# design.net
KiCad netlist of a schematic drawn in Altium Designer
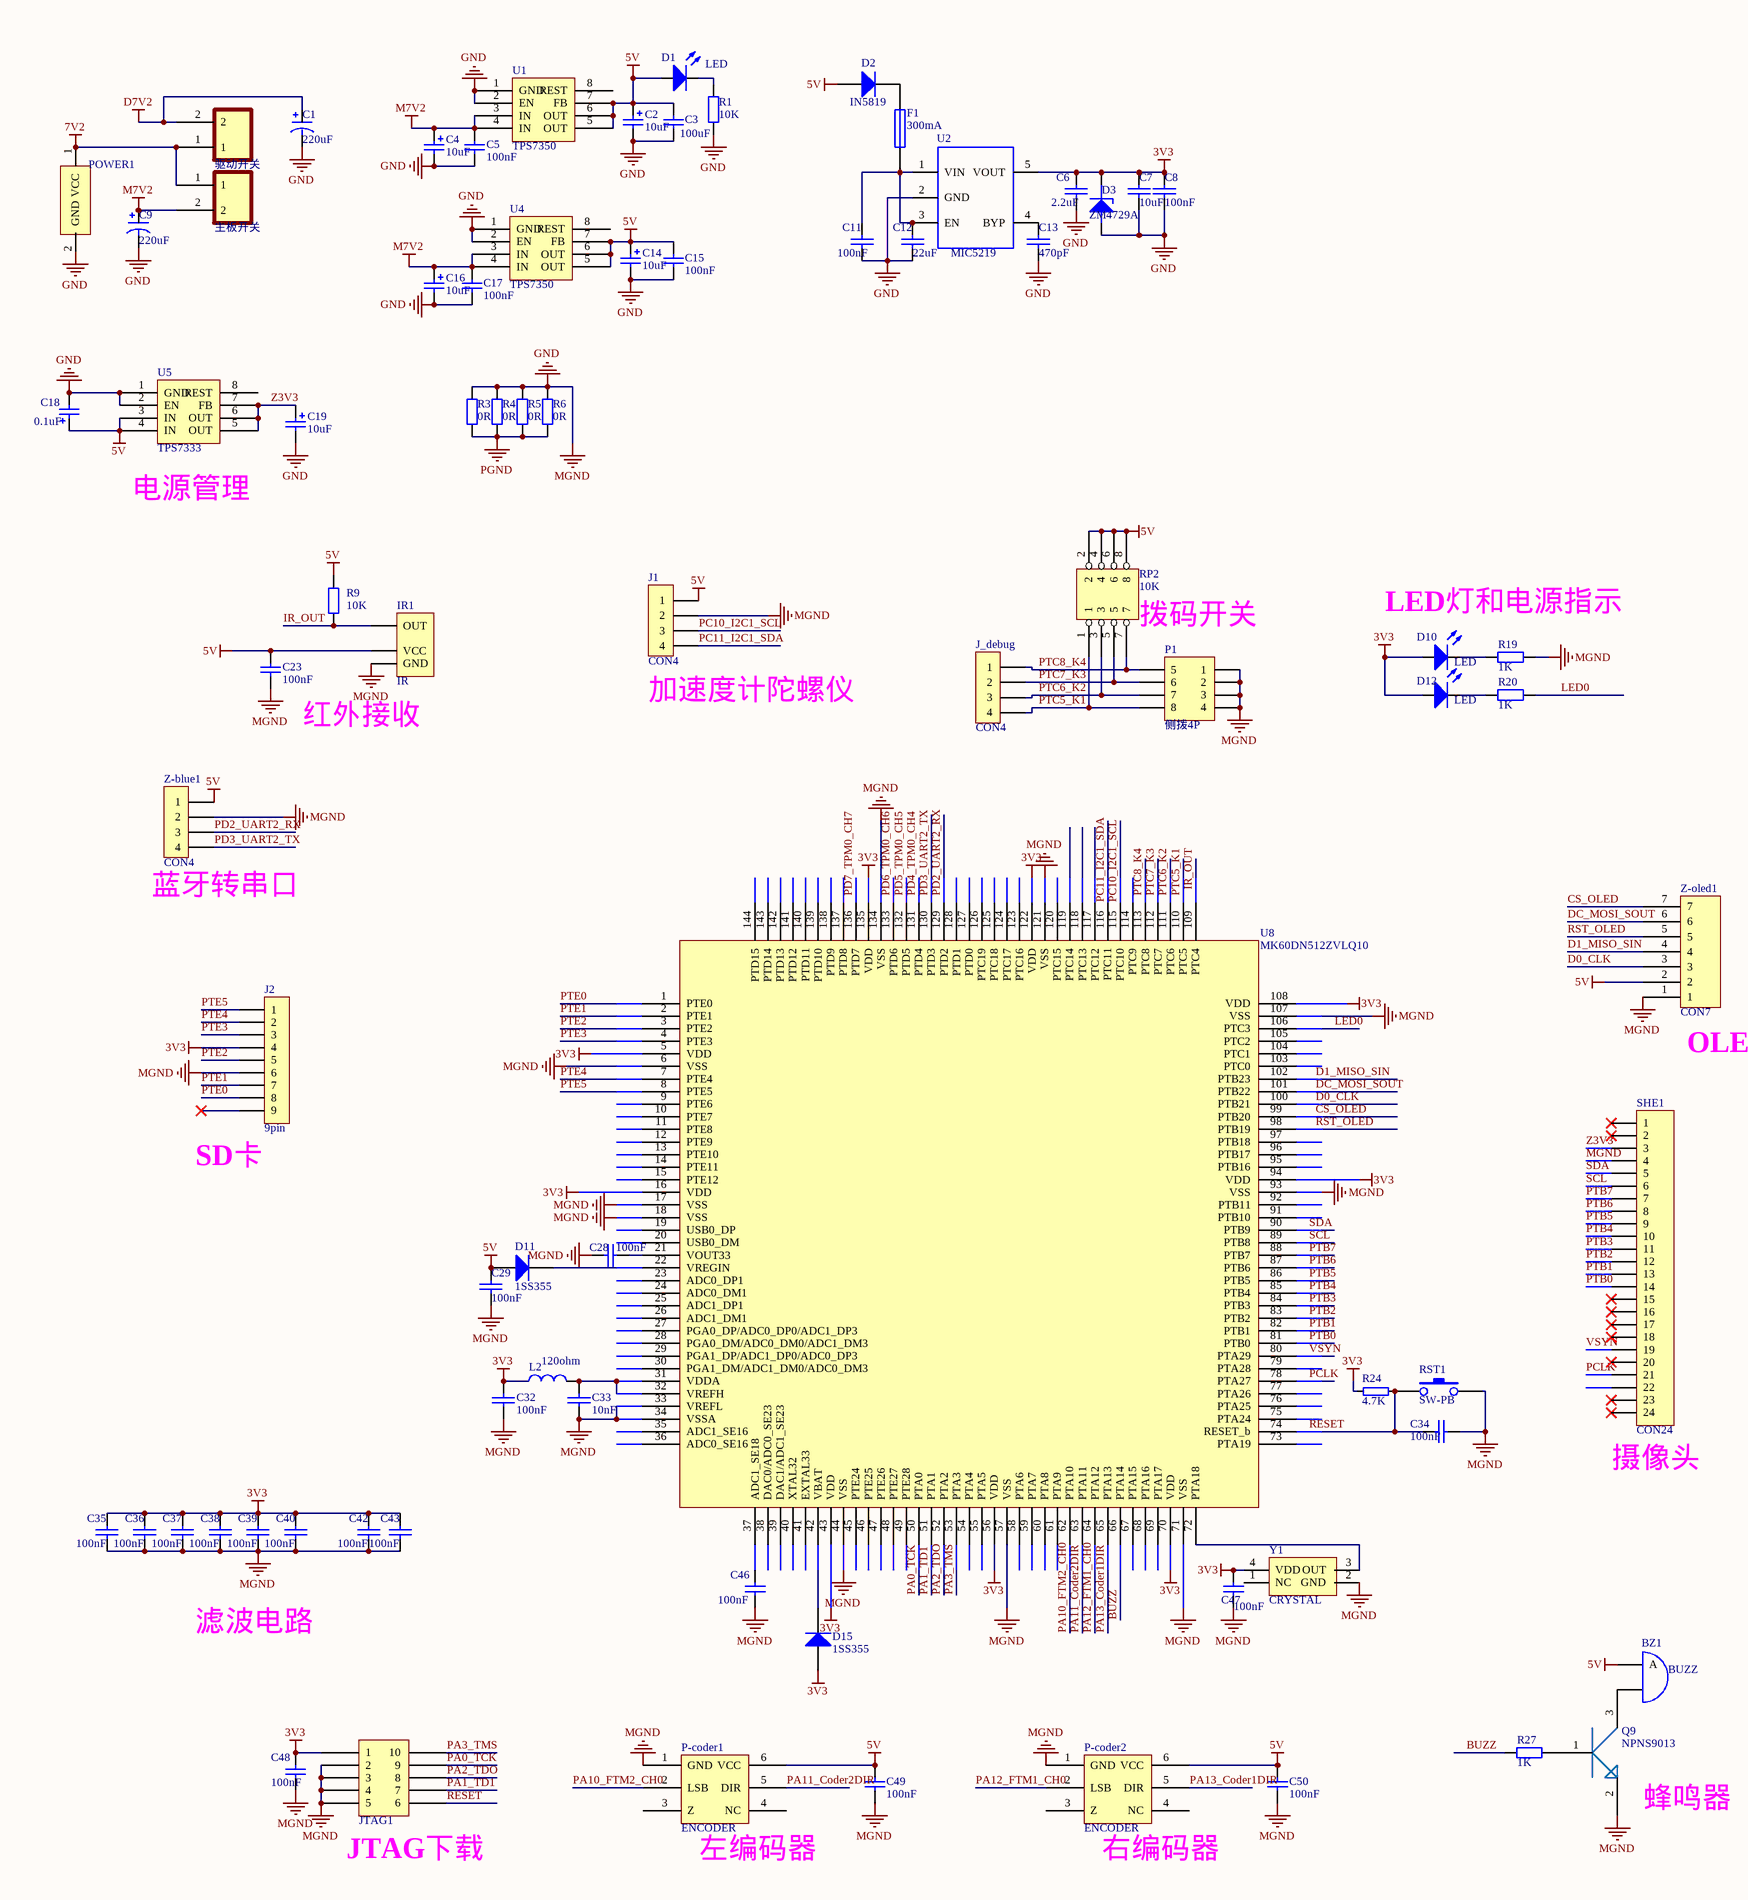
[diagram p0: 第十二届直立摄像头.SchDoc, left]
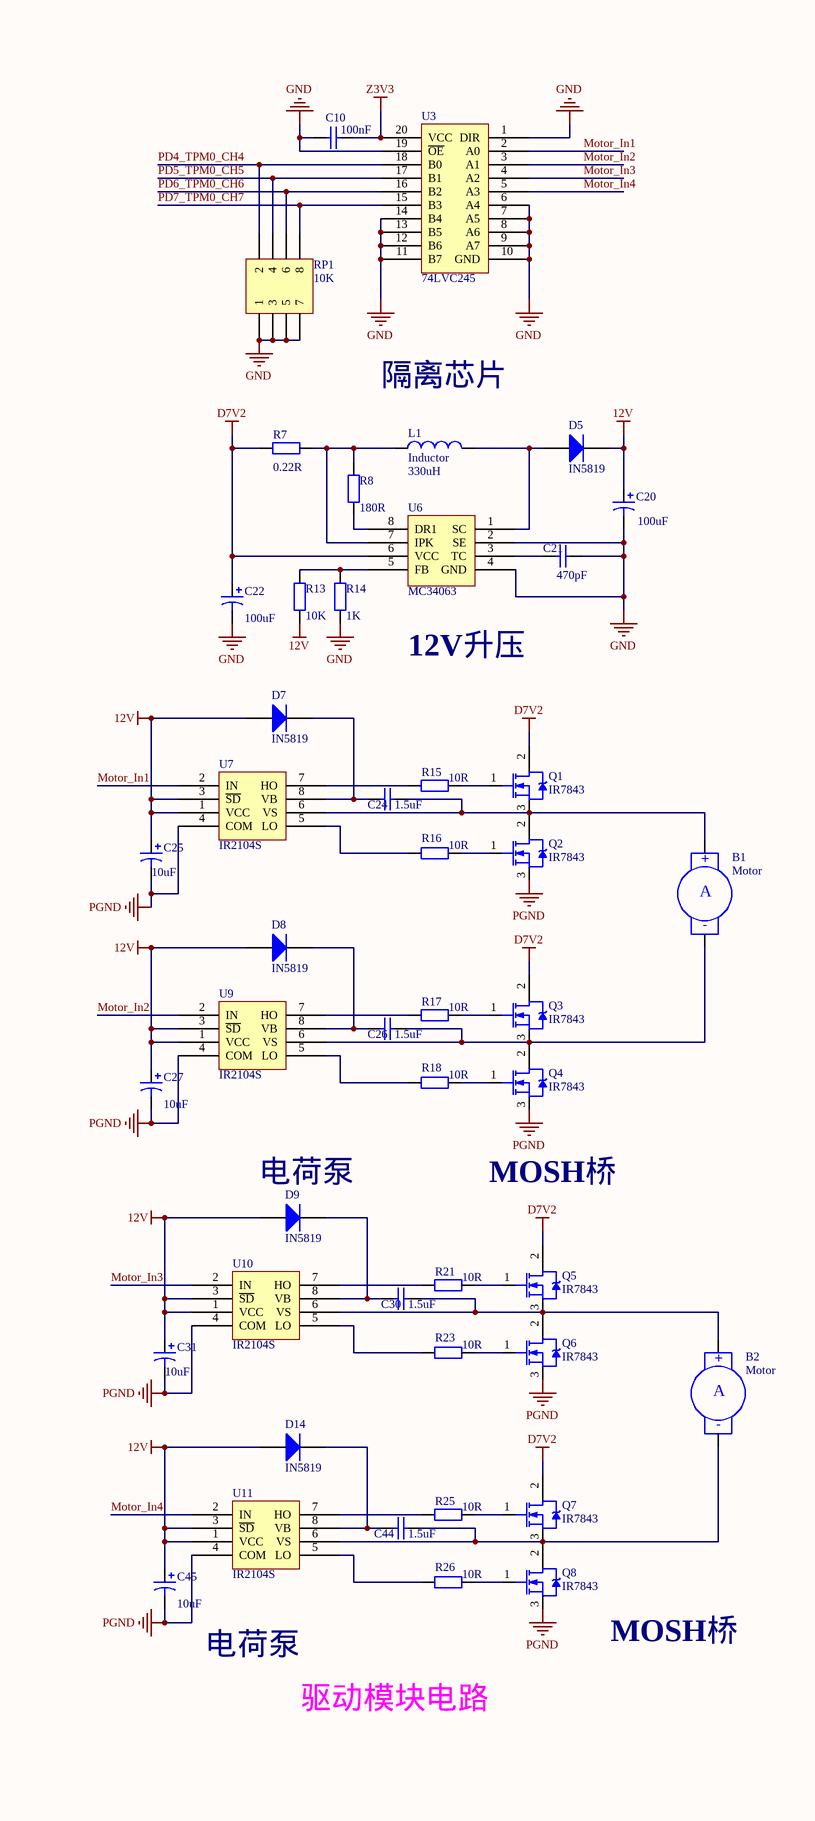
[diagram p1: 第十二届直立摄像头.SchDoc, right]

(export (version "E")
  (design (tool "Eeschema 10.0.6"))
  (components
    (comp (ref "B1")
      (value "Motor")
      (footprint "KF301-2P")
      (description "Servo Motor")
      (libsource (lib "MOS motor driving module ") (part "Motor Servo"))
    )
    (comp (ref "B2")
      (value "Motor")
      (footprint "KF301-2P")
      (description "Servo Motor")
      (libsource (lib "MOS motor driving module ") (part "Motor Servo"))
    )
    (comp (ref "BZ1") (value "BUZZ") (footprint "BUZZ") (libsource (lib "原理图库") (part "BUZZ")))
    (comp (ref "C1")
      (value "CAP2")
      (footprint "铝电解电容10*10.2")
      (description "电容带极性")
      (fields (field (name "ALTIUM_UNNAMED_1") "220uF"))
      (libsource (lib "原理图库") (part "CAP2"))
    )
    (comp (ref "C2") (value "10uF") (footprint "3216") (libsource (lib "飞思卡尔") (part "电容")))
    (comp (ref "C3")
      (value "100uF")
      (footprint "0603(1608)")
      (description "Capacitor")
      (libsource (lib "最小系统板K60P144-V4.0") (part "Cap"))
    )
    (comp (ref "C4") (value "10uF") (footprint "3216") (libsource (lib "飞思卡尔") (part "电容")))
    (comp (ref "C5")
      (value "100nF")
      (footprint "0603(1608)")
      (description "Capacitor")
      (libsource (lib "最小系统板K60P144-V4.0") (part "Cap"))
    )
    (comp (ref "C6")
      (value "2.2uF")
      (footprint "0603(1608)")
      (description "Capacitor")
      (libsource (lib "K60芯片") (part "普通电容"))
    )
    (comp (ref "C7")
      (value "10uF")
      (footprint "0603(1608)")
      (description "Capacitor")
      (libsource (lib "K60芯片") (part "普通电容"))
    )
    (comp (ref "C8")
      (value "100nF")
      (footprint "0603(1608)")
      (description "Capacitor")
      (libsource (lib "K60芯片") (part "普通电容"))
    )
    (comp (ref "C9")
      (value "CAP2")
      (footprint "铝电解电容10*10.2")
      (description "电容带极性")
      (fields (field (name "ALTIUM_UNNAMED_1") "220uF"))
      (libsource (lib "原理图库") (part "CAP2"))
    )
    (comp (ref "C10")
      (value "100nF")
      (footprint "0603(1608)")
      (description "Capacitor")
      (fields (field (name "Comment") "Cap") (field (name "PUBLISHER") "Altium Limited"))
      (libsource (lib "Miscellaneous Devices") (part "Cap"))
    )
    (comp (ref "C11")
      (value "100nF")
      (footprint "0603(1608)")
      (description "Capacitor")
      (libsource (lib "K60芯片") (part "普通电容"))
    )
    (comp (ref "C12")
      (value "22uF")
      (footprint "0603(1608)")
      (description "Capacitor")
      (libsource (lib "K60芯片") (part "普通电容"))
    )
    (comp (ref "C13")
      (value "470pF")
      (footprint "0603(1608)")
      (description "Capacitor")
      (libsource (lib "K60芯片") (part "普通电容"))
    )
    (comp (ref "C14") (value "10uF") (footprint "3216") (libsource (lib "飞思卡尔") (part "电容")))
    (comp (ref "C15")
      (value "100nF")
      (footprint "0603(1608)")
      (description "Capacitor")
      (libsource (lib "最小系统板K60P144-V4.0") (part "Cap"))
    )
    (comp (ref "C16") (value "10uF") (footprint "3216") (libsource (lib "飞思卡尔") (part "电容")))
    (comp (ref "C17")
      (value "100nF")
      (footprint "0603(1608)")
      (description "Capacitor")
      (libsource (lib "最小系统板K60P144-V4.0") (part "Cap"))
    )
    (comp (ref "C18") (value "0.1uF") (footprint "3216") (libsource (lib "飞思卡尔") (part "电容")))
    (comp (ref "C19") (value "10uF") (footprint "3216") (libsource (lib "飞思卡尔") (part "电容")))
    (comp (ref "C20")
      (value "100uF")
      (footprint "TAN-D7343")
      (description "Polarized Capacitor (Radial)")
      (fields (field (name "Comment") "Cap Pol1") (field (name "PUBLISHER") "Altium Limited"))
      (libsource (lib "Miscellaneous Devices") (part "Cap Pol1"))
    )
    (comp (ref "C21")
      (value "470pF")
      (footprint "0603(1608)")
      (description "Capacitor")
      (fields (field (name "Comment") "Cap") (field (name "PUBLISHER") "Altium Limited"))
      (libsource (lib "Miscellaneous Devices") (part "Cap"))
    )
    (comp (ref "C22")
      (value "100uF")
      (footprint "TAN-D7343")
      (description "Polarized Capacitor (Radial)")
      (fields (field (name "Comment") "Cap Pol1") (field (name "PUBLISHER") "Altium Limited"))
      (libsource (lib "Miscellaneous Devices") (part "Cap Pol1"))
    )
    (comp (ref "C23")
      (value "100nF")
      (footprint "0603(1608)")
      (description "Capacitor")
      (fields (field (name "PUBLISHER") "Altium Limited"))
      (libsource (lib "国特原理图库") (part "Cap_1"))
    )
    (comp (ref "C24")
      (value "1.5uF")
      (footprint "0603(1608)")
      (description "Capacitor")
      (fields (field (name "Comment") "Cap") (field (name "PUBLISHER") "Altium Limited"))
      (libsource (lib "Miscellaneous Devices") (part "Cap"))
    )
    (comp (ref "C25")
      (value "10uF")
      (footprint "Tan-A3216")
      (description "Polarized Capacitor (Radial)")
      (fields (field (name "Comment") "Cap Pol1") (field (name "PUBLISHER") "Altium Limited"))
      (libsource (lib "Miscellaneous Devices") (part "Cap Pol1"))
    )
    (comp (ref "C26")
      (value "1.5uF")
      (footprint "0603(1608)")
      (description "Capacitor")
      (fields (field (name "Comment") "Cap") (field (name "PUBLISHER") "Altium Limited"))
      (libsource (lib "Miscellaneous Devices") (part "Cap"))
    )
    (comp (ref "C27")
      (value "10uF")
      (footprint "Tan-A3216")
      (description "Polarized Capacitor (Radial)")
      (fields (field (name "Comment") "Cap Pol1") (field (name "PUBLISHER") "Altium Limited"))
      (libsource (lib "Miscellaneous Devices") (part "Cap Pol1"))
    )
    (comp (ref "C28")
      (value "100nF")
      (footprint "0603(1608)")
      (description "Capacitor")
      (libsource (lib "K60芯片") (part "普通电容"))
    )
    (comp (ref "C29")
      (value "100nF")
      (footprint "0603(1608)")
      (description "Capacitor")
      (libsource (lib "K60芯片") (part "普通电容"))
    )
    (comp (ref "C30")
      (value "1.5uF")
      (footprint "0603(1608)")
      (description "Capacitor")
      (fields (field (name "Comment") "Cap") (field (name "PUBLISHER") "Altium Limited"))
      (libsource (lib "Miscellaneous Devices") (part "Cap"))
    )
    (comp (ref "C31")
      (value "10uF")
      (footprint "Tan-A3216")
      (description "Polarized Capacitor (Radial)")
      (fields (field (name "Comment") "Cap Pol1") (field (name "PUBLISHER") "Altium Limited"))
      (libsource (lib "Miscellaneous Devices") (part "Cap Pol1"))
    )
    (comp (ref "C32")
      (value "100nF")
      (footprint "0603(1608)")
      (description "Capacitor")
      (libsource (lib "K60芯片") (part "普通电容"))
    )
    (comp (ref "C33")
      (value "10nF")
      (footprint "0603(1608)")
      (description "Capacitor")
      (libsource (lib "K60芯片") (part "普通电容"))
    )
    (comp (ref "C34")
      (value "100nF")
      (footprint "0603(1608)")
      (description "Capacitor")
      (libsource (lib "K60芯片") (part "普通电容"))
    )
    (comp (ref "C35")
      (value "100nF")
      (footprint "0603(1608)")
      (description "Capacitor")
      (libsource (lib "K60芯片") (part "普通电容"))
    )
    (comp (ref "C36")
      (value "100nF")
      (footprint "0603(1608)")
      (description "Capacitor")
      (libsource (lib "K60芯片") (part "普通电容"))
    )
    (comp (ref "C37")
      (value "100nF")
      (footprint "0603(1608)")
      (description "Capacitor")
      (libsource (lib "K60芯片") (part "普通电容"))
    )
    (comp (ref "C38")
      (value "100nF")
      (footprint "0603(1608)")
      (description "Capacitor")
      (libsource (lib "K60芯片") (part "普通电容"))
    )
    (comp (ref "C39")
      (value "100nF")
      (footprint "0603(1608)")
      (description "Capacitor")
      (libsource (lib "K60芯片") (part "普通电容"))
    )
    (comp (ref "C40")
      (value "100nF")
      (footprint "0603(1608)")
      (description "Capacitor")
      (libsource (lib "K60芯片") (part "普通电容"))
    )
    (comp (ref "C42")
      (value "100nF")
      (footprint "0603(1608)")
      (description "Capacitor")
      (libsource (lib "K60芯片") (part "普通电容"))
    )
    (comp (ref "C43")
      (value "100nF")
      (footprint "0603(1608)")
      (description "Capacitor")
      (libsource (lib "K60芯片") (part "普通电容"))
    )
    (comp (ref "C44")
      (value "1.5uF")
      (footprint "0603(1608)")
      (description "Capacitor")
      (fields (field (name "Comment") "Cap") (field (name "PUBLISHER") "Altium Limited"))
      (libsource (lib "Miscellaneous Devices") (part "Cap"))
    )
    (comp (ref "C45")
      (value "10uF")
      (footprint "Tan-A3216")
      (description "Polarized Capacitor (Radial)")
      (fields (field (name "Comment") "Cap Pol1") (field (name "PUBLISHER") "Altium Limited"))
      (libsource (lib "Miscellaneous Devices") (part "Cap Pol1"))
    )
    (comp (ref "C46")
      (value "100nF")
      (footprint "0603(1608)")
      (description "Capacitor")
      (fields (field (name "PUBLISHER") "Altium Limited"))
      (libsource (lib "国特原理图库") (part "Cap_1"))
    )
    (comp (ref "C47")
      (value "100nF")
      (footprint "0603(1608)")
      (description "Capacitor")
      (fields (field (name "PUBLISHER") "Altium Limited"))
      (libsource (lib "国特原理图库") (part "Cap_1"))
    )
    (comp (ref "C48")
      (value "100nF")
      (footprint "0603(1608)")
      (description "Capacitor")
      (libsource (lib "最小系统板K60P144-V4.0") (part "Cap"))
    )
    (comp (ref "C49")
      (value "100nF")
      (footprint "0603(1608)")
      (description "Capacitor")
      (libsource (lib "最小系统板K60P144-V4.0") (part "Cap"))
    )
    (comp (ref "C50")
      (value "100nF")
      (footprint "0603(1608)")
      (description "Capacitor")
      (libsource (lib "最小系统板K60P144-V4.0") (part "Cap"))
    )
    (comp (ref "D1")
      (value "LED")
      (footprint "0603LED")
      (description "Typical INFRARED GaAs LED")
      (libsource (lib "国特原理图库") (part "LED"))
    )
    (comp (ref "D2")
      (value "IN5819")
      (footprint "SS14")
      (description "Default Diode")
      (fields (field (name "PUBLISHER") "Altium Limited"))
      (libsource (lib "Miscellaneous Devices") (part "Diode"))
    )
    (comp (ref "D3")
      (value "ZM4729A")
      (footprint "LL-41")
      (description "Zener Diode")
      (libsource (lib "K60最小系统") (part "稳压二极管"))
    )
    (comp (ref "D5")
      (value "IN5819")
      (footprint "SS14")
      (description "Default Diode")
      (fields (field (name "PUBLISHER") "Altium Limited"))
      (libsource (lib "Miscellaneous Devices") (part "Diode"))
    )
    (comp (ref "D7")
      (value "IN5819")
      (footprint "SS14")
      (description "Default Diode")
      (fields (field (name "PUBLISHER") "Altium Limited"))
      (libsource (lib "Miscellaneous Devices") (part "Diode"))
    )
    (comp (ref "D8")
      (value "IN5819")
      (footprint "SS14")
      (description "Default Diode")
      (fields (field (name "PUBLISHER") "Altium Limited"))
      (libsource (lib "Miscellaneous Devices") (part "Diode"))
    )
    (comp (ref "D9")
      (value "IN5819")
      (footprint "SS14")
      (description "Default Diode")
      (fields (field (name "PUBLISHER") "Altium Limited"))
      (libsource (lib "Miscellaneous Devices") (part "Diode"))
    )
    (comp (ref "D10")
      (value "LED")
      (footprint "0603LED")
      (description "Typical INFRARED GaAs LED")
      (libsource (lib "国特原理图库") (part "LED"))
    )
    (comp (ref "D11")
      (value "1SS355")
      (footprint "0805(有极性)")
      (description "High Conductance Fast Diode")
      (fields (field (name "PUBLISHER") "Altium Limited"))
      (libsource (lib "最小系统板K60P144-V4.0") (part "Diode 1N4148"))
    )
    (comp (ref "D12")
      (value "LED")
      (footprint "0603LED")
      (description "Typical INFRARED GaAs LED")
      (libsource (lib "国特原理图库") (part "LED"))
    )
    (comp (ref "D14")
      (value "IN5819")
      (footprint "SS14")
      (description "Default Diode")
      (fields (field (name "PUBLISHER") "Altium Limited"))
      (libsource (lib "Miscellaneous Devices") (part "Diode"))
    )
    (comp (ref "D15")
      (value "1SS355")
      (footprint "0805(有极性)")
      (description "High Conductance Fast Diode")
      (fields (field (name "PUBLISHER") "Altium Limited"))
      (libsource (lib "最小系统板K60P144-V4.0") (part "Diode 1N4148"))
    )
    (comp (ref "F1")
      (value "300mA")
      (footprint "保险丝")
      (description "Fuse")
      (fields (field (name "PUBLISHER") "Altium Limited"))
      (libsource (lib "最小系统板K60P144-V4.0") (part "Fuse 1"))
    )
    (comp (ref "IR1") (value "IR") (footprint "IR2") (libsource (lib "原理图库") (part "IR_2")))
    (comp (ref "J1") (value "CON4") (footprint "CON4-1") (libsource (lib "原理图库") (part "CON4")))
    (comp (ref "J2") (value "9pin") (footprint "SD") (libsource (lib "zrobot_sch_lib") (part "9pin")))
    (comp (ref "JTAG1") (value "JTAG") (footprint "IDC5X2") (libsource (lib "国特原理图库") (part "JTAG")))
    (comp (ref "J_debug") (value "CON4") (footprint "CON4-1") (libsource (lib "原理图库") (part "CON4")))
    (comp (ref "L1")
      (value "Inductor")
      (footprint "贴片电感7*7*4")
      (fields (field (name "ALTIUM_VALUE") "330uH") (field (name "PUBLISHER") "Altium Limited"))
      (libsource (lib "Miscellaneous Devices") (part "Inductor"))
    )
    (comp (ref "L2") (value "120ohm") (footprint "0805 - duplicate") (libsource (lib "K60芯片") (part "L")))
    (comp (ref "P-coder1") (value "ENCODER") (footprint "ENCODER") (libsource (lib "原理图库") (part "ENCODER")))
    (comp (ref "P-coder2") (value "ENCODER") (footprint "ENCODER") (libsource (lib "原理图库") (part "ENCODER")))
    (comp (ref "P1") (value "侧拨4P") (footprint "侧拨4P") (libsource (lib "原理图库") (part "侧拨4P")))
    (comp (ref "POWER1") (value "~") (footprint "T槽") (libsource (lib "原理图库") (part "T槽")))
    (comp (ref "Q1")
      (value "IR7843")
      (footprint "LR7843")
      (description "N-Channel Power MOSFET")
      (fields (field (name "PUBLISHER") "Altium Limited"))
      (libsource (lib "MOS motor driving module ") (part "NMOS-2"))
    )
    (comp (ref "Q2")
      (value "IR7843")
      (footprint "LR7843")
      (description "N-Channel Power MOSFET")
      (fields (field (name "PUBLISHER") "Altium Limited"))
      (libsource (lib "MOS motor driving module ") (part "NMOS-2"))
    )
    (comp (ref "Q3")
      (value "IR7843")
      (footprint "LR7843")
      (description "N-Channel Power MOSFET")
      (fields (field (name "PUBLISHER") "Altium Limited"))
      (libsource (lib "MOS motor driving module ") (part "NMOS-2"))
    )
    (comp (ref "Q4")
      (value "IR7843")
      (footprint "LR7843")
      (description "N-Channel Power MOSFET")
      (fields (field (name "PUBLISHER") "Altium Limited"))
      (libsource (lib "MOS motor driving module ") (part "NMOS-2"))
    )
    (comp (ref "Q5")
      (value "IR7843")
      (footprint "LR7843")
      (description "N-Channel Power MOSFET")
      (fields (field (name "PUBLISHER") "Altium Limited"))
      (libsource (lib "MOS motor driving module ") (part "NMOS-2"))
    )
    (comp (ref "Q6")
      (value "IR7843")
      (footprint "LR7843")
      (description "N-Channel Power MOSFET")
      (fields (field (name "PUBLISHER") "Altium Limited"))
      (libsource (lib "MOS motor driving module ") (part "NMOS-2"))
    )
    (comp (ref "Q7")
      (value "IR7843")
      (footprint "LR7843")
      (description "N-Channel Power MOSFET")
      (fields (field (name "PUBLISHER") "Altium Limited"))
      (libsource (lib "MOS motor driving module ") (part "NMOS-2"))
    )
    (comp (ref "Q8")
      (value "IR7843")
      (footprint "LR7843")
      (description "N-Channel Power MOSFET")
      (fields (field (name "PUBLISHER") "Altium Limited"))
      (libsource (lib "MOS motor driving module ") (part "NMOS-2"))
    )
    (comp (ref "Q9") (value "NPNS9013") (footprint "S9013") (libsource (lib "原理图库") (part "S9013")))
    (comp (ref "R1")
      (value "10K")
      (footprint "0603(1608)")
      (description "Resistor")
      (fields (field (name "PUBLISHER") "Altium Limited"))
      (libsource (lib "Miscellaneous Devices") (part "Res2"))
    )
    (comp (ref "R3") (value "0R") (footprint "0805(2012)") (libsource (lib "飞思卡尔") (part "RES")))
    (comp (ref "R4") (value "0R") (footprint "0805(2012)") (libsource (lib "飞思卡尔") (part "RES")))
    (comp (ref "R5") (value "0R") (footprint "0805(2012)") (libsource (lib "飞思卡尔") (part "RES")))
    (comp (ref "R6") (value "0R") (footprint "0805(2012)") (libsource (lib "飞思卡尔") (part "RES")))
    (comp (ref "R7")
      (value "0.22R")
      (footprint "0603(1608)")
      (description "Resistor")
      (fields (field (name "Comment") "Res2") (field (name "PUBLISHER") "Altium Limited"))
      (libsource (lib "") (part "Res2_1"))
    )
    (comp (ref "R8")
      (value "180R")
      (footprint "0603(1608)")
      (description "Resistor")
      (fields (field (name "PUBLISHER") "Altium Limited"))
      (libsource (lib "Miscellaneous Devices") (part "Res2"))
    )
    (comp (ref "R9")
      (value "10K")
      (footprint "0603(1608)")
      (description "Resistor")
      (fields (field (name "Comment") "1K") (field (name "PUBLISHER") "Altium Limited"))
      (libsource (lib "国特原理图库") (part "Res2_2"))
    )
    (comp (ref "R13")
      (value "10K")
      (footprint "0603(1608)")
      (description "Resistor")
      (fields (field (name "Comment") "Res2") (field (name "PUBLISHER") "Altium Limited"))
      (libsource (lib "Miscellaneous Devices") (part "Res2"))
    )
    (comp (ref "R14")
      (value "1K")
      (footprint "0603(1608)")
      (description "Resistor")
      (fields (field (name "Comment") "Res2") (field (name "PUBLISHER") "Altium Limited"))
      (libsource (lib "Miscellaneous Devices") (part "Res2"))
    )
    (comp (ref "R15")
      (value "10R")
      (footprint "0603(1608)")
      (description "Resistor")
      (fields (field (name "Comment") "Res2") (field (name "PUBLISHER") "Altium Limited"))
      (libsource (lib "MOS motor driving module ") (part "Res2"))
    )
    (comp (ref "R16")
      (value "10R")
      (footprint "0603(1608)")
      (description "Resistor")
      (fields (field (name "Comment") "Res2") (field (name "PUBLISHER") "Altium Limited"))
      (libsource (lib "MOS motor driving module ") (part "Res2"))
    )
    (comp (ref "R17")
      (value "10R")
      (footprint "0603(1608)")
      (description "Resistor")
      (fields (field (name "Comment") "Res2") (field (name "PUBLISHER") "Altium Limited"))
      (libsource (lib "MOS motor driving module ") (part "Res2"))
    )
    (comp (ref "R18")
      (value "10R")
      (footprint "0603(1608)")
      (description "Resistor")
      (fields (field (name "Comment") "Res2") (field (name "PUBLISHER") "Altium Limited"))
      (libsource (lib "MOS motor driving module ") (part "Res2"))
    )
    (comp (ref "R19")
      (value "1K")
      (footprint "0603(1608)")
      (description "Resistor")
      (fields (field (name "PUBLISHER") "Altium Limited"))
      (libsource (lib "国特原理图库") (part "Res2_1"))
    )
    (comp (ref "R20")
      (value "1K")
      (footprint "0603(1608)")
      (description "Resistor")
      (fields (field (name "PUBLISHER") "Altium Limited"))
      (libsource (lib "国特原理图库") (part "Res2_1"))
    )
    (comp (ref "R21")
      (value "10R")
      (footprint "0603(1608)")
      (description "Resistor")
      (fields (field (name "Comment") "Res2") (field (name "PUBLISHER") "Altium Limited"))
      (libsource (lib "MOS motor driving module ") (part "Res2"))
    )
    (comp (ref "R23")
      (value "10R")
      (footprint "0603(1608)")
      (description "Resistor")
      (fields (field (name "Comment") "Res2") (field (name "PUBLISHER") "Altium Limited"))
      (libsource (lib "MOS motor driving module ") (part "Res2"))
    )
    (comp (ref "R24") (value "4.7K") (footprint "0603(1608)") (libsource (lib "K60芯片") (part "RES")))
    (comp (ref "R25")
      (value "10R")
      (footprint "0603(1608)")
      (description "Resistor")
      (fields (field (name "Comment") "Res2") (field (name "PUBLISHER") "Altium Limited"))
      (libsource (lib "MOS motor driving module ") (part "Res2"))
    )
    (comp (ref "R26")
      (value "10R")
      (footprint "0603(1608)")
      (description "Resistor")
      (fields (field (name "Comment") "Res2") (field (name "PUBLISHER") "Altium Limited"))
      (libsource (lib "MOS motor driving module ") (part "Res2"))
    )
    (comp (ref "R27")
      (value "1K")
      (footprint "0603(1608)")
      (description "Resistor")
      (fields (field (name "PUBLISHER") "Altium Limited"))
      (libsource (lib "") (part "Res2_2_1"))
    )
    (comp (ref "RP1")
      (value "10K")
      (footprint "RA_8")
      (description "Header, 4-Pin, Dual row")
      (fields (field (name "PUBLISHER") "Altium Limited"))
      (libsource (lib "Miscellaneous Connectors") (part "Header 4X2"))
    )
    (comp (ref "RP2")
      (value "HEADER4*2")
      (footprint "RA_8")
      (fields (field (name "ALTIUM_UNNAMED_1") "10K"))
      (libsource (lib "原理图库") (part "HEADER4*2"))
    )
    (comp (ref "RST1") (value "SW-PB") (footprint "SMT_BUTTON") (libsource (lib "K60芯片") (part "微动开关")))
    (comp (ref "SHE1") (value "CON24") (footprint "24P压线头") (libsource (lib "K60芯片") (part "CON24")))
    (comp (ref "U1") (value "TPS7350") (footprint "SOIC-8") (libsource (lib "飞思卡尔") (part "TPS")))
    (comp (ref "U2")
      (value "MIC5219")
      (footprint "SOT-23-5")
      (description "LDO")
      (libsource (lib "最小系统板K60P144-V4.0") (part "MIC5219"))
    )
    (comp (ref "U3")
      (value "74LVC245")
      (footprint "74LVC245 TSSOP")
      (libsource (lib "原理图库") (part "74LVC245"))
    )
    (comp (ref "U4") (value "TPS7350") (footprint "SOIC-8") (libsource (lib "飞思卡尔") (part "TPS")))
    (comp (ref "U5") (value "TPS7333") (footprint "SOIC-8") (libsource (lib "飞思卡尔") (part "TPS")))
    (comp (ref "U6") (value "MC34063") (footprint "MC34063") (libsource (lib "原理图库") (part "MC34063")))
    (comp (ref "U7")
      (value "IR2104S")
      (footprint "IR2104")
      (libsource (lib "MOS motor driving module ") (part "IR2104S"))
    )
    (comp (ref "U8")
      (value "MK60DN512ZVLQ10")
      (footprint "LQFP-144")
      (libsource (lib "K60芯片") (part "MK60DN512ZVLQ10"))
    )
    (comp (ref "U9")
      (value "IR2104S")
      (footprint "IR2104")
      (libsource (lib "MOS motor driving module ") (part "IR2104S"))
    )
    (comp (ref "U10")
      (value "IR2104S")
      (footprint "IR2104")
      (libsource (lib "MOS motor driving module ") (part "IR2104S"))
    )
    (comp (ref "U11")
      (value "IR2104S")
      (footprint "IR2104")
      (libsource (lib "MOS motor driving module ") (part "IR2104S"))
    )
    (comp (ref "Y1") (value "CRYSTAL") (footprint "SMD7050") (libsource (lib "原理图库") (part "CRYSTAL")))
    (comp (ref "Z-blue1") (value "CON4") (footprint "Bluetooth") (libsource (lib "原理图库") (part "CON4")))
    (comp (ref "Z-oled1") (value "CON7") (footprint "CON7_OLED") (libsource (lib "原理图库") (part "CON7")))
    (comp (ref "主板开关1") (value "主板开关") (footprint "船型开关-small") (libsource (lib "") (part "船型开关_1")))
    (comp (ref "驱动开关1") (value "驱动开关") (footprint "船型开关-small") (libsource (lib "国特原理图库") (part "船型开关")))
  )
  (nets
    (net (code "1") (name "/BUZZ") (class "Default")
      (node (ref "R27") (pin "2") (pinfunction "2_2") (pintype "passive"))
      (node (ref "U8") (pin "66") (pinfunction "PTA14_66") (pintype "passive"))
    )
    (net (code "2") (name "/CS_OLED") (class "Default")
      (node (ref "U8") (pin "99") (pinfunction "PTB20_99") (pintype "passive"))
      (node (ref "Z-oled1") (pin "7") (pinfunction "7_7") (pintype "passive"))
    )
    (net (code "3") (name "/D0_CLK") (class "Default")
      (node (ref "U8") (pin "100") (pinfunction "PTB21_100") (pintype "passive"))
      (node (ref "Z-oled1") (pin "3") (pinfunction "3_3") (pintype "passive"))
    )
    (net (code "4") (name "/D1_MISO_SIN") (class "Default")
      (node (ref "U8") (pin "102") (pinfunction "PTB23_102") (pintype "passive"))
      (node (ref "Z-oled1") (pin "4") (pinfunction "4_4") (pintype "passive"))
    )
    (net (code "5") (name "/DC_MOSI_SOUT") (class "Default")
      (node (ref "U8") (pin "101") (pinfunction "PTB22_101") (pintype "passive"))
      (node (ref "Z-oled1") (pin "6") (pinfunction "6_6") (pintype "passive"))
    )
    (net (code "6") (name "/IR_OUT") (class "Default")
      (node (ref "IR1") (pin "3") (pinfunction "OUT_3") (pintype "passive"))
      (node (ref "R9") (pin "1") (pinfunction "1_1") (pintype "passive"))
      (node (ref "U8") (pin "109") (pinfunction "PTC4_109") (pintype "passive"))
    )
    (net (code "7") (name "/LED0") (class "Default")
      (node (ref "R20") (pin "2") (pinfunction "2_2") (pintype "passive"))
      (node (ref "U8") (pin "106") (pinfunction "PTC3_106") (pintype "passive"))
    )
    (net (code "8") (name "/Motor_In1") (class "Default")
      (node (ref "U3") (pin "2") (pinfunction "A0_2") (pintype "passive"))
      (node (ref "U7") (pin "2") (pinfunction "IN_2") (pintype "passive"))
    )
    (net (code "9") (name "/Motor_In2") (class "Default")
      (node (ref "U3") (pin "3") (pinfunction "A1_3") (pintype "passive"))
      (node (ref "U9") (pin "2") (pinfunction "IN_2") (pintype "passive"))
    )
    (net (code "10") (name "/Motor_In3") (class "Default")
      (node (ref "U10") (pin "2") (pinfunction "IN_2") (pintype "passive"))
      (node (ref "U3") (pin "4") (pinfunction "A2_4") (pintype "passive"))
    )
    (net (code "11") (name "/Motor_In4") (class "Default")
      (node (ref "U11") (pin "2") (pinfunction "IN_2") (pintype "passive"))
      (node (ref "U3") (pin "5") (pinfunction "A3_5") (pintype "passive"))
    )
    (net (code "12") (name "/PA0_TCK") (class "Default")
      (node (ref "JTAG1") (pin "9") (pinfunction "9_9") (pintype "passive"))
      (node (ref "U8") (pin "50") (pinfunction "PTA0_50") (pintype "passive"))
    )
    (net (code "13") (name "/PA1_TD1") (class "Default")
      (node (ref "JTAG1") (pin "7") (pinfunction "7_7") (pintype "passive"))
      (node (ref "U8") (pin "51") (pinfunction "PTA1_51") (pintype "passive"))
    )
    (net (code "14") (name "/PA2_TDO") (class "Default")
      (node (ref "JTAG1") (pin "8") (pinfunction "8_8") (pintype "passive"))
      (node (ref "U8") (pin "52") (pinfunction "PTA2_52") (pintype "passive"))
    )
    (net (code "15") (name "/PA3_TMS") (class "Default")
      (node (ref "JTAG1") (pin "10") (pinfunction "10_10") (pintype "passive"))
      (node (ref "U8") (pin "53") (pinfunction "PTA3_53") (pintype "passive"))
    )
    (net (code "16") (name "/PA10_FTM2_CH0") (class "Default")
      (node (ref "P-coder1") (pin "2") (pinfunction "LSB_2") (pintype "passive"))
      (node (ref "U8") (pin "62") (pinfunction "PTA10_62") (pintype "passive"))
    )
    (net (code "17") (name "/PA11_Coder2DIR") (class "Default")
      (node (ref "P-coder1") (pin "5") (pinfunction "DIR_5") (pintype "passive"))
      (node (ref "U8") (pin "63") (pinfunction "PTA11_63") (pintype "passive"))
    )
    (net (code "18") (name "/PA12_FTM1_CH0") (class "Default")
      (node (ref "P-coder2") (pin "2") (pinfunction "LSB_2") (pintype "passive"))
      (node (ref "U8") (pin "64") (pinfunction "PTA12_64") (pintype "passive"))
    )
    (net (code "19") (name "/PA13_Coder1DIR") (class "Default")
      (node (ref "P-coder2") (pin "5") (pinfunction "DIR_5") (pintype "passive"))
      (node (ref "U8") (pin "65") (pinfunction "PTA13_65") (pintype "passive"))
    )
    (net (code "20") (name "/PC10_I2C1_SCL") (class "Default")
      (node (ref "J1") (pin "3") (pinfunction "3_3") (pintype "passive"))
      (node (ref "U8") (pin "115") (pinfunction "PTC10_115") (pintype "passive"))
    )
    (net (code "21") (name "/PC11_I2C1_SDA") (class "Default")
      (node (ref "J1") (pin "4") (pinfunction "4_4") (pintype "passive"))
      (node (ref "U8") (pin "116") (pinfunction "PTC11_116") (pintype "passive"))
    )
    (net (code "22") (name "/PCLK") (class "Default")
      (node (ref "SHE1") (pin "21") (pinfunction "21_21") (pintype "passive"))
      (node (ref "U8") (pin "78") (pinfunction "PTA27_78") (pintype "passive"))
    )
    (net (code "23") (name "/PD2_UART2_RX") (class "Default")
      (node (ref "U8") (pin "129") (pinfunction "PTD2_129") (pintype "passive"))
      (node (ref "Z-blue1") (pin "3") (pinfunction "3_3") (pintype "passive"))
    )
    (net (code "24") (name "/PD3_UART2_TX") (class "Default")
      (node (ref "U8") (pin "130") (pinfunction "PTD3_130") (pintype "passive"))
      (node (ref "Z-blue1") (pin "4") (pinfunction "4_4") (pintype "passive"))
    )
    (net (code "25") (name "/PD4_TPM0_CH4") (class "Default")
      (node (ref "RP1") (pin "2") (pinfunction "2_2") (pintype "passive"))
      (node (ref "U3") (pin "18") (pinfunction "B0_18") (pintype "passive"))
      (node (ref "U8") (pin "131") (pinfunction "PTD4_131") (pintype "passive"))
    )
    (net (code "26") (name "/PD5_TPM0_CH5") (class "Default")
      (node (ref "RP1") (pin "4") (pinfunction "4_4") (pintype "passive"))
      (node (ref "U3") (pin "17") (pinfunction "B1_17") (pintype "passive"))
      (node (ref "U8") (pin "132") (pinfunction "PTD5_132") (pintype "passive"))
    )
    (net (code "27") (name "/PD6_TPM0_CH6") (class "Default")
      (node (ref "RP1") (pin "6") (pinfunction "6_6") (pintype "passive"))
      (node (ref "U3") (pin "16") (pinfunction "B2_16") (pintype "passive"))
      (node (ref "U8") (pin "133") (pinfunction "PTD6_133") (pintype "passive"))
    )
    (net (code "28") (name "/PD7_TPM0_CH7") (class "Default")
      (node (ref "RP1") (pin "8") (pinfunction "8_8") (pintype "passive"))
      (node (ref "U3") (pin "15") (pinfunction "B3_15") (pintype "passive"))
      (node (ref "U8") (pin "136") (pinfunction "PTD7_136") (pintype "passive"))
    )
    (net (code "29") (name "/PTB0") (class "Default")
      (node (ref "SHE1") (pin "14") (pinfunction "14_14") (pintype "passive"))
      (node (ref "U8") (pin "81") (pinfunction "PTB0_81") (pintype "passive"))
    )
    (net (code "30") (name "/PTB1") (class "Default")
      (node (ref "SHE1") (pin "13") (pinfunction "13_13") (pintype "passive"))
      (node (ref "U8") (pin "82") (pinfunction "PTB1_82") (pintype "passive"))
    )
    (net (code "31") (name "/PTB2") (class "Default")
      (node (ref "SHE1") (pin "12") (pinfunction "12_12") (pintype "passive"))
      (node (ref "U8") (pin "83") (pinfunction "PTB2_83") (pintype "passive"))
    )
    (net (code "32") (name "/PTB3") (class "Default")
      (node (ref "SHE1") (pin "11") (pinfunction "11_11") (pintype "passive"))
      (node (ref "U8") (pin "84") (pinfunction "PTB3_84") (pintype "passive"))
    )
    (net (code "33") (name "/PTB4") (class "Default")
      (node (ref "SHE1") (pin "10") (pinfunction "10_10") (pintype "passive"))
      (node (ref "U8") (pin "85") (pinfunction "PTB4_85") (pintype "passive"))
    )
    (net (code "34") (name "/PTB5") (class "Default")
      (node (ref "SHE1") (pin "9") (pinfunction "9_9") (pintype "passive"))
      (node (ref "U8") (pin "86") (pinfunction "PTB5_86") (pintype "passive"))
    )
    (net (code "35") (name "/PTB6") (class "Default")
      (node (ref "SHE1") (pin "8") (pinfunction "8_8") (pintype "passive"))
      (node (ref "U8") (pin "87") (pinfunction "PTB6_87") (pintype "passive"))
    )
    (net (code "36") (name "/PTB7") (class "Default")
      (node (ref "SHE1") (pin "7") (pinfunction "7_7") (pintype "passive"))
      (node (ref "U8") (pin "88") (pinfunction "PTB7_88") (pintype "passive"))
    )
    (net (code "37") (name "/PTC5_K1") (class "Default")
      (node (ref "J_debug") (pin "4") (pinfunction "4_4") (pintype "passive"))
      (node (ref "P1") (pin "8") (pinfunction "8_8") (pintype "passive"))
      (node (ref "RP2") (pin "1") (pinfunction "1_1") (pintype "passive"))
      (node (ref "U8") (pin "110") (pinfunction "PTC5_110") (pintype "passive"))
    )
    (net (code "38") (name "/PTC6_K2") (class "Default")
      (node (ref "J_debug") (pin "3") (pinfunction "3_3") (pintype "passive"))
      (node (ref "P1") (pin "7") (pinfunction "7_7") (pintype "passive"))
      (node (ref "RP2") (pin "3") (pinfunction "3_3") (pintype "passive"))
      (node (ref "U8") (pin "111") (pinfunction "PTC6_111") (pintype "passive"))
    )
    (net (code "39") (name "/PTC7_K3") (class "Default")
      (node (ref "J_debug") (pin "2") (pinfunction "2_2") (pintype "passive"))
      (node (ref "P1") (pin "6") (pinfunction "6_6") (pintype "passive"))
      (node (ref "RP2") (pin "5") (pinfunction "5_5") (pintype "passive"))
      (node (ref "U8") (pin "112") (pinfunction "PTC7_112") (pintype "passive"))
    )
    (net (code "40") (name "/PTC8_K4") (class "Default")
      (node (ref "J_debug") (pin "1") (pinfunction "1_1") (pintype "passive"))
      (node (ref "P1") (pin "5") (pinfunction "5_5") (pintype "passive"))
      (node (ref "RP2") (pin "7") (pinfunction "7_7") (pintype "passive"))
      (node (ref "U8") (pin "113") (pinfunction "PTC8_113") (pintype "passive"))
    )
    (net (code "41") (name "/PTE0") (class "Default")
      (node (ref "J2") (pin "8") (pinfunction "8_8") (pintype "passive"))
      (node (ref "U8") (pin "1") (pinfunction "PTE0_1") (pintype "passive"))
    )
    (net (code "42") (name "/PTE1") (class "Default")
      (node (ref "J2") (pin "7") (pinfunction "7_7") (pintype "passive"))
      (node (ref "U8") (pin "2") (pinfunction "PTE1_2") (pintype "passive"))
    )
    (net (code "43") (name "/PTE2") (class "Default")
      (node (ref "J2") (pin "5") (pinfunction "5_5") (pintype "passive"))
      (node (ref "U8") (pin "3") (pinfunction "PTE2_3") (pintype "passive"))
    )
    (net (code "44") (name "/PTE3") (class "Default")
      (node (ref "J2") (pin "3") (pinfunction "3_3") (pintype "passive"))
      (node (ref "U8") (pin "4") (pinfunction "PTE3_4") (pintype "passive"))
    )
    (net (code "45") (name "/PTE4") (class "Default")
      (node (ref "J2") (pin "2") (pinfunction "2_2") (pintype "passive"))
      (node (ref "U8") (pin "7") (pinfunction "PTE4_7") (pintype "passive"))
    )
    (net (code "46") (name "/PTE5") (class "Default")
      (node (ref "J2") (pin "1") (pinfunction "1_1") (pintype "passive"))
      (node (ref "U8") (pin "8") (pinfunction "PTE5_8") (pintype "passive"))
    )
    (net (code "47") (name "/RESET") (class "Default")
      (node (ref "C34") (pin "1") (pinfunction "1_1") (pintype "passive"))
      (node (ref "JTAG1") (pin "6") (pinfunction "6_6") (pintype "passive"))
      (node (ref "R24") (pin "1") (pinfunction "1_1") (pintype "passive"))
      (node (ref "RST1") (pin "1") (pinfunction "1_1") (pintype "passive"))
      (node (ref "U8") (pin "74") (pinfunction "RESET_b_74") (pintype "passive"))
    )
    (net (code "48") (name "/RST_OLED") (class "Default")
      (node (ref "U8") (pin "98") (pinfunction "PTB19_98") (pintype "passive"))
      (node (ref "Z-oled1") (pin "5") (pinfunction "5_5") (pintype "passive"))
    )
    (net (code "49") (name "/SCL") (class "Default")
      (node (ref "SHE1") (pin "6") (pinfunction "6_6") (pintype "passive"))
      (node (ref "U8") (pin "89") (pinfunction "PTB8_89") (pintype "passive"))
    )
    (net (code "50") (name "/SDA") (class "Default")
      (node (ref "SHE1") (pin "5") (pinfunction "5_5") (pintype "passive"))
      (node (ref "U8") (pin "90") (pinfunction "PTB9_90") (pintype "passive"))
    )
    (net (code "51") (name "/VSYN") (class "Default")
      (node (ref "SHE1") (pin "19") (pinfunction "19_19") (pintype "passive"))
      (node (ref "U8") (pin "80") (pinfunction "PTA29_80") (pintype "passive"))
    )
    (net (code "52") (name "3V3") (class "Default")
      (node (ref "C32") (pin "2") (pinfunction "2_2") (pintype "passive"))
      (node (ref "C35") (pin "2") (pinfunction "2_2") (pintype "passive"))
      (node (ref "C36") (pin "2") (pinfunction "2_2") (pintype "passive"))
      (node (ref "C37") (pin "2") (pinfunction "2_2") (pintype "passive"))
      (node (ref "C38") (pin "2") (pinfunction "2_2") (pintype "passive"))
      (node (ref "C39") (pin "2") (pinfunction "2_2") (pintype "passive"))
      (node (ref "C40") (pin "2") (pinfunction "2_2") (pintype "passive"))
      (node (ref "C42") (pin "2") (pinfunction "2_2") (pintype "passive"))
      (node (ref "C43") (pin "2") (pinfunction "2_2") (pintype "passive"))
      (node (ref "C47") (pin "2") (pinfunction "2_2") (pintype "passive"))
      (node (ref "C48") (pin "2") (pinfunction "2_2") (pintype "passive"))
      (node (ref "C6") (pin "2") (pinfunction "2_2") (pintype "passive"))
      (node (ref "C7") (pin "2") (pinfunction "2_2") (pintype "passive"))
      (node (ref "C8") (pin "2") (pinfunction "2_2") (pintype "passive"))
      (node (ref "D10") (pin "1") (pinfunction "1_1") (pintype "passive"))
      (node (ref "D12") (pin "1") (pinfunction "1_1") (pintype "passive"))
      (node (ref "D15") (pin "1") (pinfunction "A_1") (pintype "passive"))
      (node (ref "D3") (pin "2") (pinfunction "B_2") (pintype "passive"))
      (node (ref "J2") (pin "4") (pinfunction "4_4") (pintype "passive"))
      (node (ref "JTAG1") (pin "1") (pinfunction "1_1") (pintype "passive"))
      (node (ref "L2") (pin "2") (pinfunction "2_2") (pintype "passive"))
      (node (ref "R24") (pin "2") (pinfunction "2_2") (pintype "passive"))
      (node (ref "U2") (pin "5") (pinfunction "VOUT_5") (pintype "passive"))
      (node (ref "U8") (pin "108") (pinfunction "VDD_108") (pintype "passive"))
      (node (ref "U8") (pin "122") (pinfunction "VDD_122") (pintype "passive"))
      (node (ref "U8") (pin "135") (pinfunction "VDD_135") (pintype "passive"))
      (node (ref "U8") (pin "16") (pinfunction "VDD_16") (pintype "passive"))
      (node (ref "U8") (pin "43") (pinfunction "VDD_43") (pintype "passive"))
      (node (ref "U8") (pin "5") (pinfunction "VDD_5") (pintype "passive"))
      (node (ref "U8") (pin "56") (pinfunction "VDD_56") (pintype "passive"))
      (node (ref "U8") (pin "70") (pinfunction "VDD_70") (pintype "passive"))
      (node (ref "U8") (pin "94") (pinfunction "VDD_94") (pintype "passive"))
      (node (ref "Y1") (pin "4") (pinfunction "VDD_4") (pintype "passive"))
    )
    (net (code "53") (name "5V") (class "Default")
      (node (ref "BZ1") (pin "1") (pinfunction "A_1") (pintype "passive"))
      (node (ref "C14") (pin "1") (pinfunction "1_1") (pintype "passive"))
      (node (ref "C15") (pin "2") (pinfunction "2_2") (pintype "passive"))
      (node (ref "C18") (pin "1") (pinfunction "1_1") (pintype "passive"))
      (node (ref "C2") (pin "1") (pinfunction "1_1") (pintype "passive"))
      (node (ref "C23") (pin "2") (pinfunction "2_2") (pintype "passive"))
      (node (ref "C29") (pin "2") (pinfunction "2_2") (pintype "passive"))
      (node (ref "C3") (pin "2") (pinfunction "2_2") (pintype "passive"))
      (node (ref "C49") (pin "1") (pinfunction "1_1") (pintype "passive"))
      (node (ref "C50") (pin "1") (pinfunction "1_1") (pintype "passive"))
      (node (ref "D1") (pin "1") (pinfunction "1_1") (pintype "passive"))
      (node (ref "D11") (pin "1") (pinfunction "A_1") (pintype "passive"))
      (node (ref "D2") (pin "1") (pinfunction "A_1") (pintype "passive"))
      (node (ref "IR1") (pin "2") (pinfunction "VCC_2") (pintype "passive"))
      (node (ref "J1") (pin "1") (pinfunction "1_1") (pintype "passive"))
      (node (ref "P-coder1") (pin "6") (pinfunction "VCC_6") (pintype "passive"))
      (node (ref "P-coder2") (pin "6") (pinfunction "VCC_6") (pintype "passive"))
      (node (ref "R9") (pin "2") (pinfunction "2_2") (pintype "passive"))
      (node (ref "RP2") (pin "2") (pinfunction "2_2") (pintype "passive"))
      (node (ref "RP2") (pin "4") (pinfunction "4_4") (pintype "passive"))
      (node (ref "RP2") (pin "6") (pinfunction "6_6") (pintype "passive"))
      (node (ref "RP2") (pin "8") (pinfunction "8_8") (pintype "passive"))
      (node (ref "U1") (pin "5") (pinfunction "OUT_5") (pintype "passive"))
      (node (ref "U1") (pin "6") (pinfunction "OUT_6") (pintype "passive"))
      (node (ref "U1") (pin "7") (pinfunction "FB_7") (pintype "passive"))
      (node (ref "U4") (pin "5") (pinfunction "OUT_5") (pintype "passive"))
      (node (ref "U4") (pin "6") (pinfunction "OUT_6") (pintype "passive"))
      (node (ref "U4") (pin "7") (pinfunction "FB_7") (pintype "passive"))
      (node (ref "U5") (pin "3") (pinfunction "IN_3") (pintype "passive"))
      (node (ref "U5") (pin "4") (pinfunction "IN_4") (pintype "passive"))
      (node (ref "Z-blue1") (pin "1") (pinfunction "1_1") (pintype "passive"))
      (node (ref "Z-oled1") (pin "2") (pinfunction "2_2") (pintype "passive"))
    )
    (net (code "54") (name "7V2") (class "Default")
      (node (ref "POWER1") (pin "1") (pinfunction "VCC_1") (pintype "passive"))
      (node (ref "主板开关1") (pin "1") (pinfunction "1_1") (pintype "passive"))
      (node (ref "驱动开关1") (pin "1") (pinfunction "1_1") (pintype "passive"))
    )
    (net (code "55") (name "12V") (class "Default")
      (node (ref "C20") (pin "1") (pinfunction "1_1") (pintype "passive"))
      (node (ref "C25") (pin "1") (pinfunction "1_1") (pintype "passive"))
      (node (ref "C27") (pin "1") (pinfunction "1_1") (pintype "passive"))
      (node (ref "C31") (pin "1") (pinfunction "1_1") (pintype "passive"))
      (node (ref "C45") (pin "1") (pinfunction "1_1") (pintype "passive"))
      (node (ref "D14") (pin "1") (pinfunction "A_1") (pintype "passive"))
      (node (ref "D5") (pin "2") (pinfunction "K_2") (pintype "passive"))
      (node (ref "D7") (pin "1") (pinfunction "A_1") (pintype "passive"))
      (node (ref "D8") (pin "1") (pinfunction "A_1") (pintype "passive"))
      (node (ref "D9") (pin "1") (pinfunction "A_1") (pintype "passive"))
      (node (ref "R13") (pin "1") (pinfunction "1_1") (pintype "passive"))
      (node (ref "U10") (pin "1") (pinfunction "VCC_1") (pintype "passive"))
      (node (ref "U10") (pin "3") (pinfunction "~{SD}_3") (pintype "passive"))
      (node (ref "U11") (pin "1") (pinfunction "VCC_1") (pintype "passive"))
      (node (ref "U11") (pin "3") (pinfunction "~{SD}_3") (pintype "passive"))
      (node (ref "U7") (pin "1") (pinfunction "VCC_1") (pintype "passive"))
      (node (ref "U7") (pin "3") (pinfunction "~{SD}_3") (pintype "passive"))
      (node (ref "U9") (pin "1") (pinfunction "VCC_1") (pintype "passive"))
      (node (ref "U9") (pin "3") (pinfunction "~{SD}_3") (pintype "passive"))
    )
    (net (code "56") (name "D7V2") (class "Default")
      (node (ref "C1") (pin "1") (pinfunction "1_1") (pintype "passive"))
      (node (ref "C22") (pin "1") (pinfunction "1_1") (pintype "passive"))
      (node (ref "Q1") (pin "2") (pinfunction "D_2") (pintype "passive"))
      (node (ref "Q3") (pin "2") (pinfunction "D_2") (pintype "passive"))
      (node (ref "Q5") (pin "2") (pinfunction "D_2") (pintype "passive"))
      (node (ref "Q7") (pin "2") (pinfunction "D_2") (pintype "passive"))
      (node (ref "R7") (pin "2") (pinfunction "2_2") (pintype "passive"))
      (node (ref "U6") (pin "6") (pinfunction "VCC_6") (pintype "passive"))
      (node (ref "驱动开关1") (pin "2") (pinfunction "2_2") (pintype "passive"))
    )
    (net (code "57") (name "GND") (class "Default")
      (node (ref "C1") (pin "2") (pinfunction "2_2") (pintype "passive"))
      (node (ref "C10") (pin "1") (pinfunction "1_1") (pintype "passive"))
      (node (ref "C11") (pin "1") (pinfunction "1_1") (pintype "passive"))
      (node (ref "C12") (pin "1") (pinfunction "1_1") (pintype "passive"))
      (node (ref "C13") (pin "1") (pinfunction "1_1") (pintype "passive"))
      (node (ref "C14") (pin "2") (pinfunction "2_2") (pintype "passive"))
      (node (ref "C15") (pin "1") (pinfunction "1_1") (pintype "passive"))
      (node (ref "C16") (pin "2") (pinfunction "2_2") (pintype "passive"))
      (node (ref "C17") (pin "1") (pinfunction "1_1") (pintype "passive"))
      (node (ref "C18") (pin "2") (pinfunction "2_2") (pintype "passive"))
      (node (ref "C19") (pin "2") (pinfunction "2_2") (pintype "passive"))
      (node (ref "C2") (pin "2") (pinfunction "2_2") (pintype "passive"))
      (node (ref "C20") (pin "2") (pinfunction "2_2") (pintype "passive"))
      (node (ref "C21") (pin "2") (pinfunction "2_2") (pintype "passive"))
      (node (ref "C22") (pin "2") (pinfunction "2_2") (pintype "passive"))
      (node (ref "C23") (pin "1") (pinfunction "1_1") (pintype "passive"))
      (node (ref "C28") (pin "1") (pinfunction "1_1") (pintype "passive"))
      (node (ref "C29") (pin "1") (pinfunction "1_1") (pintype "passive"))
      (node (ref "C3") (pin "1") (pinfunction "1_1") (pintype "passive"))
      (node (ref "C32") (pin "1") (pinfunction "1_1") (pintype "passive"))
      (node (ref "C33") (pin "1") (pinfunction "1_1") (pintype "passive"))
      (node (ref "C34") (pin "2") (pinfunction "2_2") (pintype "passive"))
      (node (ref "C35") (pin "1") (pinfunction "1_1") (pintype "passive"))
      (node (ref "C36") (pin "1") (pinfunction "1_1") (pintype "passive"))
      (node (ref "C37") (pin "1") (pinfunction "1_1") (pintype "passive"))
      (node (ref "C38") (pin "1") (pinfunction "1_1") (pintype "passive"))
      (node (ref "C39") (pin "1") (pinfunction "1_1") (pintype "passive"))
      (node (ref "C4") (pin "2") (pinfunction "2_2") (pintype "passive"))
      (node (ref "C40") (pin "1") (pinfunction "1_1") (pintype "passive"))
      (node (ref "C42") (pin "1") (pinfunction "1_1") (pintype "passive"))
      (node (ref "C43") (pin "1") (pinfunction "1_1") (pintype "passive"))
      (node (ref "C46") (pin "1") (pinfunction "1_1") (pintype "passive"))
      (node (ref "C47") (pin "1") (pinfunction "1_1") (pintype "passive"))
      (node (ref "C48") (pin "1") (pinfunction "1_1") (pintype "passive"))
      (node (ref "C49") (pin "2") (pinfunction "2_2") (pintype "passive"))
      (node (ref "C5") (pin "2") (pinfunction "2_2") (pintype "passive"))
      (node (ref "C50") (pin "2") (pinfunction "2_2") (pintype "passive"))
      (node (ref "C6") (pin "1") (pinfunction "1_1") (pintype "passive"))
      (node (ref "C7") (pin "1") (pinfunction "1_1") (pintype "passive"))
      (node (ref "C8") (pin "1") (pinfunction "1_1") (pintype "passive"))
      (node (ref "C9") (pin "2") (pinfunction "2_2") (pintype "passive"))
      (node (ref "D3") (pin "1") (pinfunction "A_1") (pintype "passive"))
      (node (ref "IR1") (pin "1") (pinfunction "GND_1") (pintype "passive"))
      (node (ref "J1") (pin "2") (pinfunction "2_2") (pintype "passive"))
      (node (ref "J2") (pin "6") (pinfunction "6_6") (pintype "passive"))
      (node (ref "JTAG1") (pin "2") (pinfunction "2_2") (pintype "passive"))
      (node (ref "JTAG1") (pin "3") (pinfunction "3_3") (pintype "passive"))
      (node (ref "JTAG1") (pin "4") (pinfunction "4_4") (pintype "passive"))
      (node (ref "JTAG1") (pin "5") (pinfunction "5_5") (pintype "passive"))
      (node (ref "P-coder1") (pin "1") (pinfunction "GND_1") (pintype "passive"))
      (node (ref "P-coder2") (pin "1") (pinfunction "GND_1") (pintype "passive"))
      (node (ref "P1") (pin "1") (pinfunction "1_1") (pintype "passive"))
      (node (ref "P1") (pin "2") (pinfunction "2_2") (pintype "passive"))
      (node (ref "P1") (pin "3") (pinfunction "3_3") (pintype "passive"))
      (node (ref "P1") (pin "4") (pinfunction "4_4") (pintype "passive"))
      (node (ref "POWER1") (pin "2") (pinfunction "GND_2") (pintype "passive"))
      (node (ref "Q9") (pin "2") (pinfunction "2_2") (pintype "passive"))
      (node (ref "R1") (pin "1") (pinfunction "1_1") (pintype "passive"))
      (node (ref "R14") (pin "1") (pinfunction "1_1") (pintype "passive"))
      (node (ref "R19") (pin "2") (pinfunction "2_2") (pintype "passive"))
      (node (ref "R3") (pin "2") (pinfunction "2_2") (pintype "passive"))
      (node (ref "R4") (pin "2") (pinfunction "2_2") (pintype "passive"))
      (node (ref "R5") (pin "2") (pinfunction "2_2") (pintype "passive"))
      (node (ref "R6") (pin "2") (pinfunction "2_2") (pintype "passive"))
      (node (ref "RP1") (pin "1") (pinfunction "1_1") (pintype "passive"))
      (node (ref "RP1") (pin "3") (pinfunction "3_3") (pintype "passive"))
      (node (ref "RP1") (pin "5") (pinfunction "5_5") (pintype "passive"))
      (node (ref "RP1") (pin "7") (pinfunction "7_7") (pintype "passive"))
      (node (ref "RST1") (pin "2") (pinfunction "2_2") (pintype "passive"))
      (node (ref "SHE1") (pin "4") (pinfunction "4_4") (pintype "passive"))
      (node (ref "U1") (pin "1") (pinfunction "GND_1") (pintype "passive"))
      (node (ref "U1") (pin "2") (pinfunction "EN_2") (pintype "passive"))
      (node (ref "U2") (pin "2") (pinfunction "GND_2") (pintype "passive"))
      (node (ref "U3") (pin "1") (pinfunction "DIR_1") (pintype "passive"))
      (node (ref "U3") (pin "10") (pinfunction "GND_10") (pintype "passive"))
      (node (ref "U3") (pin "11") (pinfunction "B7_11") (pintype "passive"))
      (node (ref "U3") (pin "12") (pinfunction "B6_12") (pintype "passive"))
      (node (ref "U3") (pin "13") (pinfunction "B5_13") (pintype "passive"))
      (node (ref "U3") (pin "14") (pinfunction "B4_14") (pintype "passive"))
      (node (ref "U3") (pin "19") (pinfunction "~{OE}_19") (pintype "passive"))
      (node (ref "U3") (pin "6") (pinfunction "A4_6") (pintype "passive"))
      (node (ref "U3") (pin "7") (pinfunction "A5_7") (pintype "passive"))
      (node (ref "U3") (pin "8") (pinfunction "A6_8") (pintype "passive"))
      (node (ref "U3") (pin "9") (pinfunction "A7_9") (pintype "passive"))
      (node (ref "U4") (pin "1") (pinfunction "GND_1") (pintype "passive"))
      (node (ref "U4") (pin "2") (pinfunction "EN_2") (pintype "passive"))
      (node (ref "U5") (pin "1") (pinfunction "GND_1") (pintype "passive"))
      (node (ref "U5") (pin "2") (pinfunction "EN_2") (pintype "passive"))
      (node (ref "U6") (pin "2") (pinfunction "SE_2") (pintype "passive"))
      (node (ref "U6") (pin "4") (pinfunction "GND_4") (pintype "passive"))
      (node (ref "U8") (pin "107") (pinfunction "VSS_107") (pintype "passive"))
      (node (ref "U8") (pin "121") (pinfunction "VSS_121") (pintype "passive"))
      (node (ref "U8") (pin "134") (pinfunction "VSS_134") (pintype "passive"))
      (node (ref "U8") (pin "17") (pinfunction "VSS_17") (pintype "passive"))
      (node (ref "U8") (pin "18") (pinfunction "VSS_18") (pintype "passive"))
      (node (ref "U8") (pin "33") (pinfunction "VREFL_33") (pintype "passive"))
      (node (ref "U8") (pin "34") (pinfunction "VSSA_34") (pintype "passive"))
      (node (ref "U8") (pin "44") (pinfunction "VSS_44") (pintype "passive"))
      (node (ref "U8") (pin "57") (pinfunction "VSS_57") (pintype "passive"))
      (node (ref "U8") (pin "6") (pinfunction "VSS_6") (pintype "passive"))
      (node (ref "U8") (pin "71") (pinfunction "VSS_71") (pintype "passive"))
      (node (ref "U8") (pin "93") (pinfunction "VSS_93") (pintype "passive"))
      (node (ref "Y1") (pin "2") (pinfunction "GND_2") (pintype "passive"))
      (node (ref "Z-blue1") (pin "2") (pinfunction "2_2") (pintype "passive"))
      (node (ref "Z-oled1") (pin "1") (pinfunction "1_1") (pintype "passive"))
    )
    (net (code "58") (name "M7V2") (class "Default")
      (node (ref "C16") (pin "1") (pinfunction "1_1") (pintype "passive"))
      (node (ref "C17") (pin "2") (pinfunction "2_2") (pintype "passive"))
      (node (ref "C4") (pin "1") (pinfunction "1_1") (pintype "passive"))
      (node (ref "C5") (pin "1") (pinfunction "1_1") (pintype "passive"))
      (node (ref "C9") (pin "1") (pinfunction "1_1") (pintype "passive"))
      (node (ref "U1") (pin "3") (pinfunction "IN_3") (pintype "passive"))
      (node (ref "U1") (pin "4") (pinfunction "IN_4") (pintype "passive"))
      (node (ref "U4") (pin "3") (pinfunction "IN_3") (pintype "passive"))
      (node (ref "U4") (pin "4") (pinfunction "IN_4") (pintype "passive"))
      (node (ref "主板开关1") (pin "2") (pinfunction "2_2") (pintype "passive"))
    )
    (net (code "59") (name "Net-(B1-+)") (class "Default")
      (node (ref "B1") (pin "1") (pinfunction "+_1") (pintype "passive"))
      (node (ref "C24") (pin "2") (pinfunction "2_2") (pintype "passive"))
      (node (ref "Q1") (pin "3") (pinfunction "S_3") (pintype "passive"))
      (node (ref "Q2") (pin "2") (pinfunction "D_2") (pintype "passive"))
      (node (ref "U7") (pin "6") (pinfunction "VS_6") (pintype "passive"))
    )
    (net (code "60") (name "Net-(B1--)") (class "Default")
      (node (ref "B1") (pin "2") (pinfunction "-_2") (pintype "passive"))
      (node (ref "C26") (pin "2") (pinfunction "2_2") (pintype "passive"))
      (node (ref "Q3") (pin "3") (pinfunction "S_3") (pintype "passive"))
      (node (ref "Q4") (pin "2") (pinfunction "D_2") (pintype "passive"))
      (node (ref "U9") (pin "6") (pinfunction "VS_6") (pintype "passive"))
    )
    (net (code "61") (name "Net-(B2-+)") (class "Default")
      (node (ref "B2") (pin "1") (pinfunction "+_1") (pintype "passive"))
      (node (ref "C30") (pin "2") (pinfunction "2_2") (pintype "passive"))
      (node (ref "Q5") (pin "3") (pinfunction "S_3") (pintype "passive"))
      (node (ref "Q6") (pin "2") (pinfunction "D_2") (pintype "passive"))
      (node (ref "U10") (pin "6") (pinfunction "VS_6") (pintype "passive"))
    )
    (net (code "62") (name "Net-(B2--)") (class "Default")
      (node (ref "B2") (pin "2") (pinfunction "-_2") (pintype "passive"))
      (node (ref "C44") (pin "2") (pinfunction "2_2") (pintype "passive"))
      (node (ref "Q7") (pin "3") (pinfunction "S_3") (pintype "passive"))
      (node (ref "Q8") (pin "2") (pinfunction "D_2") (pintype "passive"))
      (node (ref "U11") (pin "6") (pinfunction "VS_6") (pintype "passive"))
    )
    (net (code "63") (name "Net-(BZ1-B)") (class "Default")
      (node (ref "BZ1") (pin "2") (pinfunction "B_2") (pintype "passive"))
      (node (ref "Q9") (pin "3") (pinfunction "3_3") (pintype "passive"))
    )
    (net (code "64") (name "Net-(D1-Pad2)") (class "Default")
      (node (ref "D1") (pin "2") (pinfunction "2_2") (pintype "passive"))
      (node (ref "R1") (pin "2") (pinfunction "2_2") (pintype "passive"))
    )
    (net (code "65") (name "Net-(D2-K)") (class "Default")
      (node (ref "D2") (pin "2") (pinfunction "K_2") (pintype "passive"))
      (node (ref "F1") (pin "2") (pinfunction "2_2") (pintype "passive"))
    )
    (net (code "66") (name "Net-(D5-A)") (class "Default")
      (node (ref "D5") (pin "1") (pinfunction "A_1") (pintype "passive"))
      (node (ref "L1") (pin "2") (pinfunction "2_2") (pintype "passive"))
      (node (ref "U6") (pin "1") (pinfunction "SC_1") (pintype "passive"))
    )
    (net (code "67") (name "Net-(D7-K)") (class "Default")
      (node (ref "C24") (pin "1") (pinfunction "1_1") (pintype "passive"))
      (node (ref "D7") (pin "2") (pinfunction "K_2") (pintype "passive"))
      (node (ref "U7") (pin "8") (pinfunction "VB_8") (pintype "passive"))
    )
    (net (code "68") (name "Net-(D8-K)") (class "Default")
      (node (ref "C26") (pin "1") (pinfunction "1_1") (pintype "passive"))
      (node (ref "D8") (pin "2") (pinfunction "K_2") (pintype "passive"))
      (node (ref "U9") (pin "8") (pinfunction "VB_8") (pintype "passive"))
    )
    (net (code "69") (name "Net-(D9-K)") (class "Default")
      (node (ref "C30") (pin "1") (pinfunction "1_1") (pintype "passive"))
      (node (ref "D9") (pin "2") (pinfunction "K_2") (pintype "passive"))
      (node (ref "U10") (pin "8") (pinfunction "VB_8") (pintype "passive"))
    )
    (net (code "70") (name "Net-(D10-Pad2)") (class "Default")
      (node (ref "D10") (pin "2") (pinfunction "2_2") (pintype "passive"))
      (node (ref "R19") (pin "1") (pinfunction "1_1") (pintype "passive"))
    )
    (net (code "71") (name "Net-(D11-K)") (class "Default")
      (node (ref "D11") (pin "2") (pinfunction "K_2") (pintype "passive"))
      (node (ref "U8") (pin "22") (pinfunction "VREGIN_22") (pintype "passive"))
    )
    (net (code "72") (name "Net-(D12-Pad2)") (class "Default")
      (node (ref "D12") (pin "2") (pinfunction "2_2") (pintype "passive"))
      (node (ref "R20") (pin "1") (pinfunction "1_1") (pintype "passive"))
    )
    (net (code "73") (name "Net-(D14-K)") (class "Default")
      (node (ref "C44") (pin "1") (pinfunction "1_1") (pintype "passive"))
      (node (ref "D14") (pin "2") (pinfunction "K_2") (pintype "passive"))
      (node (ref "U11") (pin "8") (pinfunction "VB_8") (pintype "passive"))
    )
    (net (code "74") (name "Net-(D15-K)") (class "Default")
      (node (ref "D15") (pin "2") (pinfunction "K_2") (pintype "passive"))
      (node (ref "U8") (pin "42") (pinfunction "VBAT_42") (pintype "passive"))
    )
    (net (code "75") (name "Net-(Q1-G)") (class "Default")
      (node (ref "Q1") (pin "1") (pinfunction "G_1") (pintype "passive"))
      (node (ref "R15") (pin "2") (pinfunction "2_2") (pintype "passive"))
    )
    (net (code "76") (name "Net-(Q2-G)") (class "Default")
      (node (ref "Q2") (pin "1") (pinfunction "G_1") (pintype "passive"))
      (node (ref "R16") (pin "2") (pinfunction "2_2") (pintype "passive"))
    )
    (net (code "77") (name "Net-(Q3-G)") (class "Default")
      (node (ref "Q3") (pin "1") (pinfunction "G_1") (pintype "passive"))
      (node (ref "R17") (pin "2") (pinfunction "2_2") (pintype "passive"))
    )
    (net (code "78") (name "Net-(Q4-G)") (class "Default")
      (node (ref "Q4") (pin "1") (pinfunction "G_1") (pintype "passive"))
      (node (ref "R18") (pin "2") (pinfunction "2_2") (pintype "passive"))
    )
    (net (code "79") (name "Net-(Q5-G)") (class "Default")
      (node (ref "Q5") (pin "1") (pinfunction "G_1") (pintype "passive"))
      (node (ref "R21") (pin "2") (pinfunction "2_2") (pintype "passive"))
    )
    (net (code "80") (name "Net-(Q6-G)") (class "Default")
      (node (ref "Q6") (pin "1") (pinfunction "G_1") (pintype "passive"))
      (node (ref "R23") (pin "2") (pinfunction "2_2") (pintype "passive"))
    )
    (net (code "81") (name "Net-(Q7-G)") (class "Default")
      (node (ref "Q7") (pin "1") (pinfunction "G_1") (pintype "passive"))
      (node (ref "R25") (pin "2") (pinfunction "2_2") (pintype "passive"))
    )
    (net (code "82") (name "Net-(Q8-G)") (class "Default")
      (node (ref "Q8") (pin "1") (pinfunction "G_1") (pintype "passive"))
      (node (ref "R26") (pin "2") (pinfunction "2_2") (pintype "passive"))
    )
    (net (code "83") (name "Net-(Q9-Pad1)") (class "Default")
      (node (ref "Q9") (pin "1") (pinfunction "1_1") (pintype "passive"))
      (node (ref "R27") (pin "1") (pinfunction "1_1") (pintype "passive"))
    )
    (net (code "84") (name "Net-(U2-BYP)") (class "Default")
      (node (ref "C13") (pin "2") (pinfunction "2_2") (pintype "passive"))
      (node (ref "U2") (pin "4") (pinfunction "BYP_4") (pintype "passive"))
    )
    (net (code "85") (name "Net-(U2-EN)") (class "Default")
      (node (ref "C11") (pin "2") (pinfunction "2_2") (pintype "passive"))
      (node (ref "C12") (pin "2") (pinfunction "2_2") (pintype "passive"))
      (node (ref "F1") (pin "1") (pinfunction "1_1") (pintype "passive"))
      (node (ref "U2") (pin "1") (pinfunction "VIN_1") (pintype "passive"))
      (node (ref "U2") (pin "3") (pinfunction "EN_3") (pintype "passive"))
    )
    (net (code "86") (name "Net-(U6-DR1)") (class "Default")
      (node (ref "R8") (pin "1") (pinfunction "1_1") (pintype "passive"))
      (node (ref "U6") (pin "8") (pinfunction "DR1_8") (pintype "passive"))
    )
    (net (code "87") (name "Net-(U6-FB)") (class "Default")
      (node (ref "R13") (pin "2") (pinfunction "2_2") (pintype "passive"))
      (node (ref "R14") (pin "2") (pinfunction "2_2") (pintype "passive"))
      (node (ref "U6") (pin "5") (pinfunction "FB_5") (pintype "passive"))
    )
    (net (code "88") (name "Net-(U6-IPK)") (class "Default")
      (node (ref "L1") (pin "1") (pinfunction "1_1") (pintype "passive"))
      (node (ref "R7") (pin "1") (pinfunction "1_1") (pintype "passive"))
      (node (ref "R8") (pin "2") (pinfunction "2_2") (pintype "passive"))
      (node (ref "U6") (pin "7") (pinfunction "IPK_7") (pintype "passive"))
    )
    (net (code "89") (name "Net-(U6-TC)") (class "Default")
      (node (ref "C21") (pin "1") (pinfunction "1_1") (pintype "passive"))
      (node (ref "U6") (pin "3") (pinfunction "TC_3") (pintype "passive"))
    )
    (net (code "90") (name "Net-(U7-HO)") (class "Default")
      (node (ref "R15") (pin "1") (pinfunction "1_1") (pintype "passive"))
      (node (ref "U7") (pin "7") (pinfunction "HO_7") (pintype "passive"))
    )
    (net (code "91") (name "Net-(U7-LO)") (class "Default")
      (node (ref "R16") (pin "1") (pinfunction "1_1") (pintype "passive"))
      (node (ref "U7") (pin "5") (pinfunction "LO_5") (pintype "passive"))
    )
    (net (code "92") (name "Net-(U8-ADC1_SE18)") (class "Default")
      (node (ref "C46") (pin "2") (pinfunction "2_2") (pintype "passive"))
      (node (ref "U8") (pin "37") (pinfunction "ADC1_SE18_37") (pintype "passive"))
    )
    (net (code "93") (name "Net-(U8-PTA18)") (class "Default")
      (node (ref "U8") (pin "72") (pinfunction "PTA18_72") (pintype "passive"))
      (node (ref "Y1") (pin "3") (pinfunction "OUT_3") (pintype "passive"))
    )
    (net (code "94") (name "Net-(U8-VDDA)") (class "Default")
      (node (ref "C33") (pin "2") (pinfunction "2_2") (pintype "passive"))
      (node (ref "L2") (pin "1") (pinfunction "1_1") (pintype "passive"))
      (node (ref "U8") (pin "31") (pinfunction "VDDA_31") (pintype "passive"))
      (node (ref "U8") (pin "32") (pinfunction "VREFH_32") (pintype "passive"))
    )
    (net (code "95") (name "Net-(U8-VOUT33)") (class "Default")
      (node (ref "C28") (pin "2") (pinfunction "2_2") (pintype "passive"))
      (node (ref "U8") (pin "21") (pinfunction "VOUT33_21") (pintype "passive"))
    )
    (net (code "96") (name "Net-(U9-HO)") (class "Default")
      (node (ref "R17") (pin "1") (pinfunction "1_1") (pintype "passive"))
      (node (ref "U9") (pin "7") (pinfunction "HO_7") (pintype "passive"))
    )
    (net (code "97") (name "Net-(U9-LO)") (class "Default")
      (node (ref "R18") (pin "1") (pinfunction "1_1") (pintype "passive"))
      (node (ref "U9") (pin "5") (pinfunction "LO_5") (pintype "passive"))
    )
    (net (code "98") (name "Net-(U10-HO)") (class "Default")
      (node (ref "R21") (pin "1") (pinfunction "1_1") (pintype "passive"))
      (node (ref "U10") (pin "7") (pinfunction "HO_7") (pintype "passive"))
    )
    (net (code "99") (name "Net-(U10-LO)") (class "Default")
      (node (ref "R23") (pin "1") (pinfunction "1_1") (pintype "passive"))
      (node (ref "U10") (pin "5") (pinfunction "LO_5") (pintype "passive"))
    )
    (net (code "100") (name "Net-(U11-HO)") (class "Default")
      (node (ref "R25") (pin "1") (pinfunction "1_1") (pintype "passive"))
      (node (ref "U11") (pin "7") (pinfunction "HO_7") (pintype "passive"))
    )
    (net (code "101") (name "Net-(U11-LO)") (class "Default")
      (node (ref "R26") (pin "1") (pinfunction "1_1") (pintype "passive"))
      (node (ref "U11") (pin "5") (pinfunction "LO_5") (pintype "passive"))
    )
    (net (code "102") (name "PGND") (class "Default")
      (node (ref "C25") (pin "2") (pinfunction "2_2") (pintype "passive"))
      (node (ref "C27") (pin "2") (pinfunction "2_2") (pintype "passive"))
      (node (ref "C31") (pin "2") (pinfunction "2_2") (pintype "passive"))
      (node (ref "C45") (pin "2") (pinfunction "2_2") (pintype "passive"))
      (node (ref "Q2") (pin "3") (pinfunction "S_3") (pintype "passive"))
      (node (ref "Q4") (pin "3") (pinfunction "S_3") (pintype "passive"))
      (node (ref "Q6") (pin "3") (pinfunction "S_3") (pintype "passive"))
      (node (ref "Q8") (pin "3") (pinfunction "S_3") (pintype "passive"))
      (node (ref "R3") (pin "1") (pinfunction "1_1") (pintype "passive"))
      (node (ref "R4") (pin "1") (pinfunction "1_1") (pintype "passive"))
      (node (ref "R5") (pin "1") (pinfunction "1_1") (pintype "passive"))
      (node (ref "R6") (pin "1") (pinfunction "1_1") (pintype "passive"))
      (node (ref "U10") (pin "4") (pinfunction "COM_4") (pintype "passive"))
      (node (ref "U11") (pin "4") (pinfunction "COM_4") (pintype "passive"))
      (node (ref "U7") (pin "4") (pinfunction "COM_4") (pintype "passive"))
      (node (ref "U9") (pin "4") (pinfunction "COM_4") (pintype "passive"))
    )
    (net (code "103") (name "Z3V3") (class "Default")
      (node (ref "C10") (pin "2") (pinfunction "2_2") (pintype "passive"))
      (node (ref "C19") (pin "1") (pinfunction "1_1") (pintype "passive"))
      (node (ref "SHE1") (pin "3") (pinfunction "3_3") (pintype "passive"))
      (node (ref "U3") (pin "20") (pinfunction "VCC_20") (pintype "passive"))
      (node (ref "U5") (pin "5") (pinfunction "OUT_5") (pintype "passive"))
      (node (ref "U5") (pin "6") (pinfunction "OUT_6") (pintype "passive"))
      (node (ref "U5") (pin "7") (pinfunction "FB_7") (pintype "passive"))
    )
    (net (code "104") (name "unconnected-(J2-Pad9)") (class "Default")
      (node (ref "J2") (pin "9") (pinfunction "9_9") (pintype "passive+no_connect"))
    )
    (net (code "105") (name "unconnected-(P-coder1-NC-Pad4)") (class "Default")
      (node (ref "P-coder1") (pin "4") (pinfunction "NC_4") (pintype "passive"))
    )
    (net (code "106") (name "unconnected-(P-coder1-Z-Pad3)") (class "Default")
      (node (ref "P-coder1") (pin "3") (pinfunction "Z_3") (pintype "passive"))
    )
    (net (code "107") (name "unconnected-(P-coder2-NC-Pad4)") (class "Default")
      (node (ref "P-coder2") (pin "4") (pinfunction "NC_4") (pintype "passive"))
    )
    (net (code "108") (name "unconnected-(P-coder2-Z-Pad3)") (class "Default")
      (node (ref "P-coder2") (pin "3") (pinfunction "Z_3") (pintype "passive"))
    )
    (net (code "109") (name "unconnected-(SHE1-Pad1)") (class "Default")
      (node (ref "SHE1") (pin "1") (pinfunction "1_1") (pintype "passive+no_connect"))
    )
    (net (code "110") (name "unconnected-(SHE1-Pad2)") (class "Default")
      (node (ref "SHE1") (pin "2") (pinfunction "2_2") (pintype "passive+no_connect"))
    )
    (net (code "111") (name "unconnected-(SHE1-Pad15)") (class "Default")
      (node (ref "SHE1") (pin "15") (pinfunction "15_15") (pintype "passive+no_connect"))
    )
    (net (code "112") (name "unconnected-(SHE1-Pad16)") (class "Default")
      (node (ref "SHE1") (pin "16") (pinfunction "16_16") (pintype "passive+no_connect"))
    )
    (net (code "113") (name "unconnected-(SHE1-Pad17)") (class "Default")
      (node (ref "SHE1") (pin "17") (pinfunction "17_17") (pintype "passive+no_connect"))
    )
    (net (code "114") (name "unconnected-(SHE1-Pad18)") (class "Default")
      (node (ref "SHE1") (pin "18") (pinfunction "18_18") (pintype "passive+no_connect"))
    )
    (net (code "115") (name "unconnected-(SHE1-Pad20)") (class "Default")
      (node (ref "SHE1") (pin "20") (pinfunction "20_20") (pintype "passive+no_connect"))
    )
    (net (code "116") (name "unconnected-(SHE1-Pad22)") (class "Default")
      (node (ref "SHE1") (pin "22") (pinfunction "22_22") (pintype "passive"))
    )
    (net (code "117") (name "unconnected-(SHE1-Pad23)") (class "Default")
      (node (ref "SHE1") (pin "23") (pinfunction "23_23") (pintype "passive+no_connect"))
    )
    (net (code "118") (name "unconnected-(SHE1-Pad24)") (class "Default")
      (node (ref "SHE1") (pin "24") (pinfunction "24_24") (pintype "passive+no_connect"))
    )
    (net (code "119") (name "unconnected-(U1-REST-Pad8)") (class "Default")
      (node (ref "U1") (pin "8") (pinfunction "REST_8") (pintype "passive"))
    )
    (net (code "120") (name "unconnected-(U4-REST-Pad8)") (class "Default")
      (node (ref "U4") (pin "8") (pinfunction "REST_8") (pintype "passive"))
    )
    (net (code "121") (name "unconnected-(U5-REST-Pad8)") (class "Default")
      (node (ref "U5") (pin "8") (pinfunction "REST_8") (pintype "passive"))
    )
    (net (code "122") (name "unconnected-(U8-ADC0_DM1-Pad24)") (class "Default")
      (node (ref "U8") (pin "24") (pinfunction "ADC0_DM1_24") (pintype "passive"))
    )
    (net (code "123") (name "unconnected-(U8-ADC0_DP1-Pad23)") (class "Default")
      (node (ref "U8") (pin "23") (pinfunction "ADC0_DP1_23") (pintype "passive"))
    )
    (net (code "124") (name "unconnected-(U8-ADC0_SE16-Pad36)") (class "Default")
      (node (ref "U8") (pin "36") (pinfunction "ADC0_SE16_36") (pintype "passive"))
    )
    (net (code "125") (name "unconnected-(U8-ADC1_DM1-Pad26)") (class "Default")
      (node (ref "U8") (pin "26") (pinfunction "ADC1_DM1_26") (pintype "passive"))
    )
    (net (code "126") (name "unconnected-(U8-ADC1_DP1-Pad25)") (class "Default")
      (node (ref "U8") (pin "25") (pinfunction "ADC1_DP1_25") (pintype "passive"))
    )
    (net (code "127") (name "unconnected-(U8-ADC1_SE16-Pad35)") (class "Default")
      (node (ref "U8") (pin "35") (pinfunction "ADC1_SE16_35") (pintype "passive"))
    )
    (net (code "128") (name "unconnected-(U8-DAC0{slash}ADC0_SE23-Pad38)") (class "Default")
      (node (ref "U8") (pin "38") (pinfunction "DAC0/ADC0_SE23_38") (pintype "passive"))
    )
    (net (code "129") (name "unconnected-(U8-DAC1{slash}ADC1_SE23-Pad39)") (class "Default")
      (node (ref "U8") (pin "39") (pinfunction "DAC1/ADC1_SE23_39") (pintype "passive"))
    )
    (net (code "130") (name "unconnected-(U8-EXTAL33-Pad41)") (class "Default")
      (node (ref "U8") (pin "41") (pinfunction "EXTAL33_41") (pintype "passive"))
    )
    (net (code "131") (name "unconnected-(U8-PGA0_DM{slash}ADC0_DM0{slash}ADC1_DM3-Pad28)") (class "Default")
      (node (ref "U8") (pin "28") (pinfunction "PGA0_DM/ADC0_DM0/ADC1_DM3_28") (pintype "passive"))
    )
    (net (code "132") (name "unconnected-(U8-PGA0_DP{slash}ADC0_DP0{slash}ADC1_DP3-Pad27)") (class "Default")
      (node (ref "U8") (pin "27") (pinfunction "PGA0_DP/ADC0_DP0/ADC1_DP3_27") (pintype "passive"))
    )
    (net (code "133") (name "unconnected-(U8-PGA1_DM{slash}ADC1_DM0{slash}ADC0_DM3-Pad30)") (class "Default")
      (node (ref "U8") (pin "30") (pinfunction "PGA1_DM/ADC1_DM0/ADC0_DM3_30") (pintype "passive"))
    )
    (net (code "134") (name "unconnected-(U8-PGA1_DP{slash}ADC1_DP0{slash}ADC0_DP3-Pad29)") (class "Default")
      (node (ref "U8") (pin "29") (pinfunction "PGA1_DP/ADC1_DP0/ADC0_DP3_29") (pintype "passive"))
    )
    (net (code "135") (name "unconnected-(U8-PTA4-Pad54)") (class "Default")
      (node (ref "U8") (pin "54") (pinfunction "PTA4_54") (pintype "passive"))
    )
    (net (code "136") (name "unconnected-(U8-PTA5-Pad55)") (class "Default")
      (node (ref "U8") (pin "55") (pinfunction "PTA5_55") (pintype "passive"))
    )
    (net (code "137") (name "unconnected-(U8-PTA6-Pad58)") (class "Default")
      (node (ref "U8") (pin "58") (pinfunction "PTA6_58") (pintype "passive"))
    )
    (net (code "138") (name "unconnected-(U8-PTA7-Pad59)") (class "Default")
      (node (ref "U8") (pin "59") (pinfunction "PTA7_59") (pintype "passive"))
    )
    (net (code "139") (name "unconnected-(U8-PTA8-Pad60)") (class "Default")
      (node (ref "U8") (pin "60") (pinfunction "PTA8_60") (pintype "passive"))
    )
    (net (code "140") (name "unconnected-(U8-PTA9-Pad61)") (class "Default")
      (node (ref "U8") (pin "61") (pinfunction "PTA9_61") (pintype "passive"))
    )
    (net (code "141") (name "unconnected-(U8-PTA15-Pad67)") (class "Default")
      (node (ref "U8") (pin "67") (pinfunction "PTA15_67") (pintype "passive"))
    )
    (net (code "142") (name "unconnected-(U8-PTA16-Pad68)") (class "Default")
      (node (ref "U8") (pin "68") (pinfunction "PTA16_68") (pintype "passive"))
    )
    (net (code "143") (name "unconnected-(U8-PTA17-Pad69)") (class "Default")
      (node (ref "U8") (pin "69") (pinfunction "PTA17_69") (pintype "passive"))
    )
    (net (code "144") (name "unconnected-(U8-PTA19-Pad73)") (class "Default")
      (node (ref "U8") (pin "73") (pinfunction "PTA19_73") (pintype "passive"))
    )
    (net (code "145") (name "unconnected-(U8-PTA24-Pad75)") (class "Default")
      (node (ref "U8") (pin "75") (pinfunction "PTA24_75") (pintype "passive"))
    )
    (net (code "146") (name "unconnected-(U8-PTA25-Pad76)") (class "Default")
      (node (ref "U8") (pin "76") (pinfunction "PTA25_76") (pintype "passive"))
    )
    (net (code "147") (name "unconnected-(U8-PTA26-Pad77)") (class "Default")
      (node (ref "U8") (pin "77") (pinfunction "PTA26_77") (pintype "passive"))
    )
    (net (code "148") (name "unconnected-(U8-PTA28-Pad79)") (class "Default")
      (node (ref "U8") (pin "79") (pinfunction "PTA28_79") (pintype "passive"))
    )
    (net (code "149") (name "unconnected-(U8-PTB10-Pad91)") (class "Default")
      (node (ref "U8") (pin "91") (pinfunction "PTB10_91") (pintype "passive"))
    )
    (net (code "150") (name "unconnected-(U8-PTB11-Pad92)") (class "Default")
      (node (ref "U8") (pin "92") (pinfunction "PTB11_92") (pintype "passive"))
    )
    (net (code "151") (name "unconnected-(U8-PTB16-Pad95)") (class "Default")
      (node (ref "U8") (pin "95") (pinfunction "PTB16_95") (pintype "passive"))
    )
    (net (code "152") (name "unconnected-(U8-PTB17-Pad96)") (class "Default")
      (node (ref "U8") (pin "96") (pinfunction "PTB17_96") (pintype "passive"))
    )
    (net (code "153") (name "unconnected-(U8-PTB18-Pad97)") (class "Default")
      (node (ref "U8") (pin "97") (pinfunction "PTB18_97") (pintype "passive"))
    )
    (net (code "154") (name "unconnected-(U8-PTC0-Pad103)") (class "Default")
      (node (ref "U8") (pin "103") (pinfunction "PTC0_103") (pintype "passive"))
    )
    (net (code "155") (name "unconnected-(U8-PTC1-Pad104)") (class "Default")
      (node (ref "U8") (pin "104") (pinfunction "PTC1_104") (pintype "passive"))
    )
    (net (code "156") (name "unconnected-(U8-PTC2-Pad105)") (class "Default")
      (node (ref "U8") (pin "105") (pinfunction "PTC2_105") (pintype "passive"))
    )
    (net (code "157") (name "unconnected-(U8-PTC9-Pad114)") (class "Default")
      (node (ref "U8") (pin "114") (pinfunction "PTC9_114") (pintype "passive"))
    )
    (net (code "158") (name "unconnected-(U8-PTC12-Pad117)") (class "Default")
      (node (ref "U8") (pin "117") (pinfunction "PTC12_117") (pintype "passive"))
    )
    (net (code "159") (name "unconnected-(U8-PTC13-Pad118)") (class "Default")
      (node (ref "U8") (pin "118") (pinfunction "PTC13_118") (pintype "passive"))
    )
    (net (code "160") (name "unconnected-(U8-PTC14-Pad119)") (class "Default")
      (node (ref "U8") (pin "119") (pinfunction "PTC14_119") (pintype "passive"))
    )
    (net (code "161") (name "unconnected-(U8-PTC15-Pad120)") (class "Default")
      (node (ref "U8") (pin "120") (pinfunction "PTC15_120") (pintype "passive"))
    )
    (net (code "162") (name "unconnected-(U8-PTC16-Pad123)") (class "Default")
      (node (ref "U8") (pin "123") (pinfunction "PTC16_123") (pintype "passive"))
    )
    (net (code "163") (name "unconnected-(U8-PTC17-Pad124)") (class "Default")
      (node (ref "U8") (pin "124") (pinfunction "PTC17_124") (pintype "passive"))
    )
    (net (code "164") (name "unconnected-(U8-PTC18-Pad125)") (class "Default")
      (node (ref "U8") (pin "125") (pinfunction "PTC18_125") (pintype "passive"))
    )
    (net (code "165") (name "unconnected-(U8-PTC19-Pad126)") (class "Default")
      (node (ref "U8") (pin "126") (pinfunction "PTC19_126") (pintype "passive"))
    )
    (net (code "166") (name "unconnected-(U8-PTD0-Pad127)") (class "Default")
      (node (ref "U8") (pin "127") (pinfunction "PTD0_127") (pintype "passive"))
    )
    (net (code "167") (name "unconnected-(U8-PTD1-Pad128)") (class "Default")
      (node (ref "U8") (pin "128") (pinfunction "PTD1_128") (pintype "passive"))
    )
    (net (code "168") (name "unconnected-(U8-PTD8-Pad137)") (class "Default")
      (node (ref "U8") (pin "137") (pinfunction "PTD8_137") (pintype "passive"))
    )
    (net (code "169") (name "unconnected-(U8-PTD9-Pad138)") (class "Default")
      (node (ref "U8") (pin "138") (pinfunction "PTD9_138") (pintype "passive"))
    )
    (net (code "170") (name "unconnected-(U8-PTD10-Pad139)") (class "Default")
      (node (ref "U8") (pin "139") (pinfunction "PTD10_139") (pintype "passive"))
    )
    (net (code "171") (name "unconnected-(U8-PTD11-Pad140)") (class "Default")
      (node (ref "U8") (pin "140") (pinfunction "PTD11_140") (pintype "passive"))
    )
    (net (code "172") (name "unconnected-(U8-PTD12-Pad141)") (class "Default")
      (node (ref "U8") (pin "141") (pinfunction "PTD12_141") (pintype "passive"))
    )
    (net (code "173") (name "unconnected-(U8-PTD13-Pad142)") (class "Default")
      (node (ref "U8") (pin "142") (pinfunction "PTD13_142") (pintype "passive"))
    )
    (net (code "174") (name "unconnected-(U8-PTD14-Pad143)") (class "Default")
      (node (ref "U8") (pin "143") (pinfunction "PTD14_143") (pintype "passive"))
    )
    (net (code "175") (name "unconnected-(U8-PTD15-Pad144)") (class "Default")
      (node (ref "U8") (pin "144") (pinfunction "PTD15_144") (pintype "passive"))
    )
    (net (code "176") (name "unconnected-(U8-PTE6-Pad9)") (class "Default")
      (node (ref "U8") (pin "9") (pinfunction "PTE6_9") (pintype "passive"))
    )
    (net (code "177") (name "unconnected-(U8-PTE7-Pad10)") (class "Default")
      (node (ref "U8") (pin "10") (pinfunction "PTE7_10") (pintype "passive"))
    )
    (net (code "178") (name "unconnected-(U8-PTE8-Pad11)") (class "Default")
      (node (ref "U8") (pin "11") (pinfunction "PTE8_11") (pintype "passive"))
    )
    (net (code "179") (name "unconnected-(U8-PTE9-Pad12)") (class "Default")
      (node (ref "U8") (pin "12") (pinfunction "PTE9_12") (pintype "passive"))
    )
    (net (code "180") (name "unconnected-(U8-PTE10-Pad13)") (class "Default")
      (node (ref "U8") (pin "13") (pinfunction "PTE10_13") (pintype "passive"))
    )
    (net (code "181") (name "unconnected-(U8-PTE11-Pad14)") (class "Default")
      (node (ref "U8") (pin "14") (pinfunction "PTE11_14") (pintype "passive"))
    )
    (net (code "182") (name "unconnected-(U8-PTE12-Pad15)") (class "Default")
      (node (ref "U8") (pin "15") (pinfunction "PTE12_15") (pintype "passive"))
    )
    (net (code "183") (name "unconnected-(U8-PTE24-Pad45)") (class "Default")
      (node (ref "U8") (pin "45") (pinfunction "PTE24_45") (pintype "passive"))
    )
    (net (code "184") (name "unconnected-(U8-PTE25-Pad46)") (class "Default")
      (node (ref "U8") (pin "46") (pinfunction "PTE25_46") (pintype "passive"))
    )
    (net (code "185") (name "unconnected-(U8-PTE26-Pad47)") (class "Default")
      (node (ref "U8") (pin "47") (pinfunction "PTE26_47") (pintype "passive"))
    )
    (net (code "186") (name "unconnected-(U8-PTE27-Pad48)") (class "Default")
      (node (ref "U8") (pin "48") (pinfunction "PTE27_48") (pintype "passive"))
    )
    (net (code "187") (name "unconnected-(U8-PTE28-Pad49)") (class "Default")
      (node (ref "U8") (pin "49") (pinfunction "PTE28_49") (pintype "passive"))
    )
    (net (code "188") (name "unconnected-(U8-USB0_DM-Pad20)") (class "Default")
      (node (ref "U8") (pin "20") (pinfunction "USB0_DM_20") (pintype "passive"))
    )
    (net (code "189") (name "unconnected-(U8-USB0_DP-Pad19)") (class "Default")
      (node (ref "U8") (pin "19") (pinfunction "USB0_DP_19") (pintype "passive"))
    )
    (net (code "190") (name "unconnected-(U8-XTAL32-Pad40)") (class "Default")
      (node (ref "U8") (pin "40") (pinfunction "XTAL32_40") (pintype "passive"))
    )
    (net (code "191") (name "unconnected-(Y1-NC-Pad1)") (class "Default")
      (node (ref "Y1") (pin "1") (pinfunction "NC_1") (pintype "passive"))
    )
  )
)
